# Pc_z80_senza_arduino.net
KiCad netlist of a schematic drawn in EasyEDA
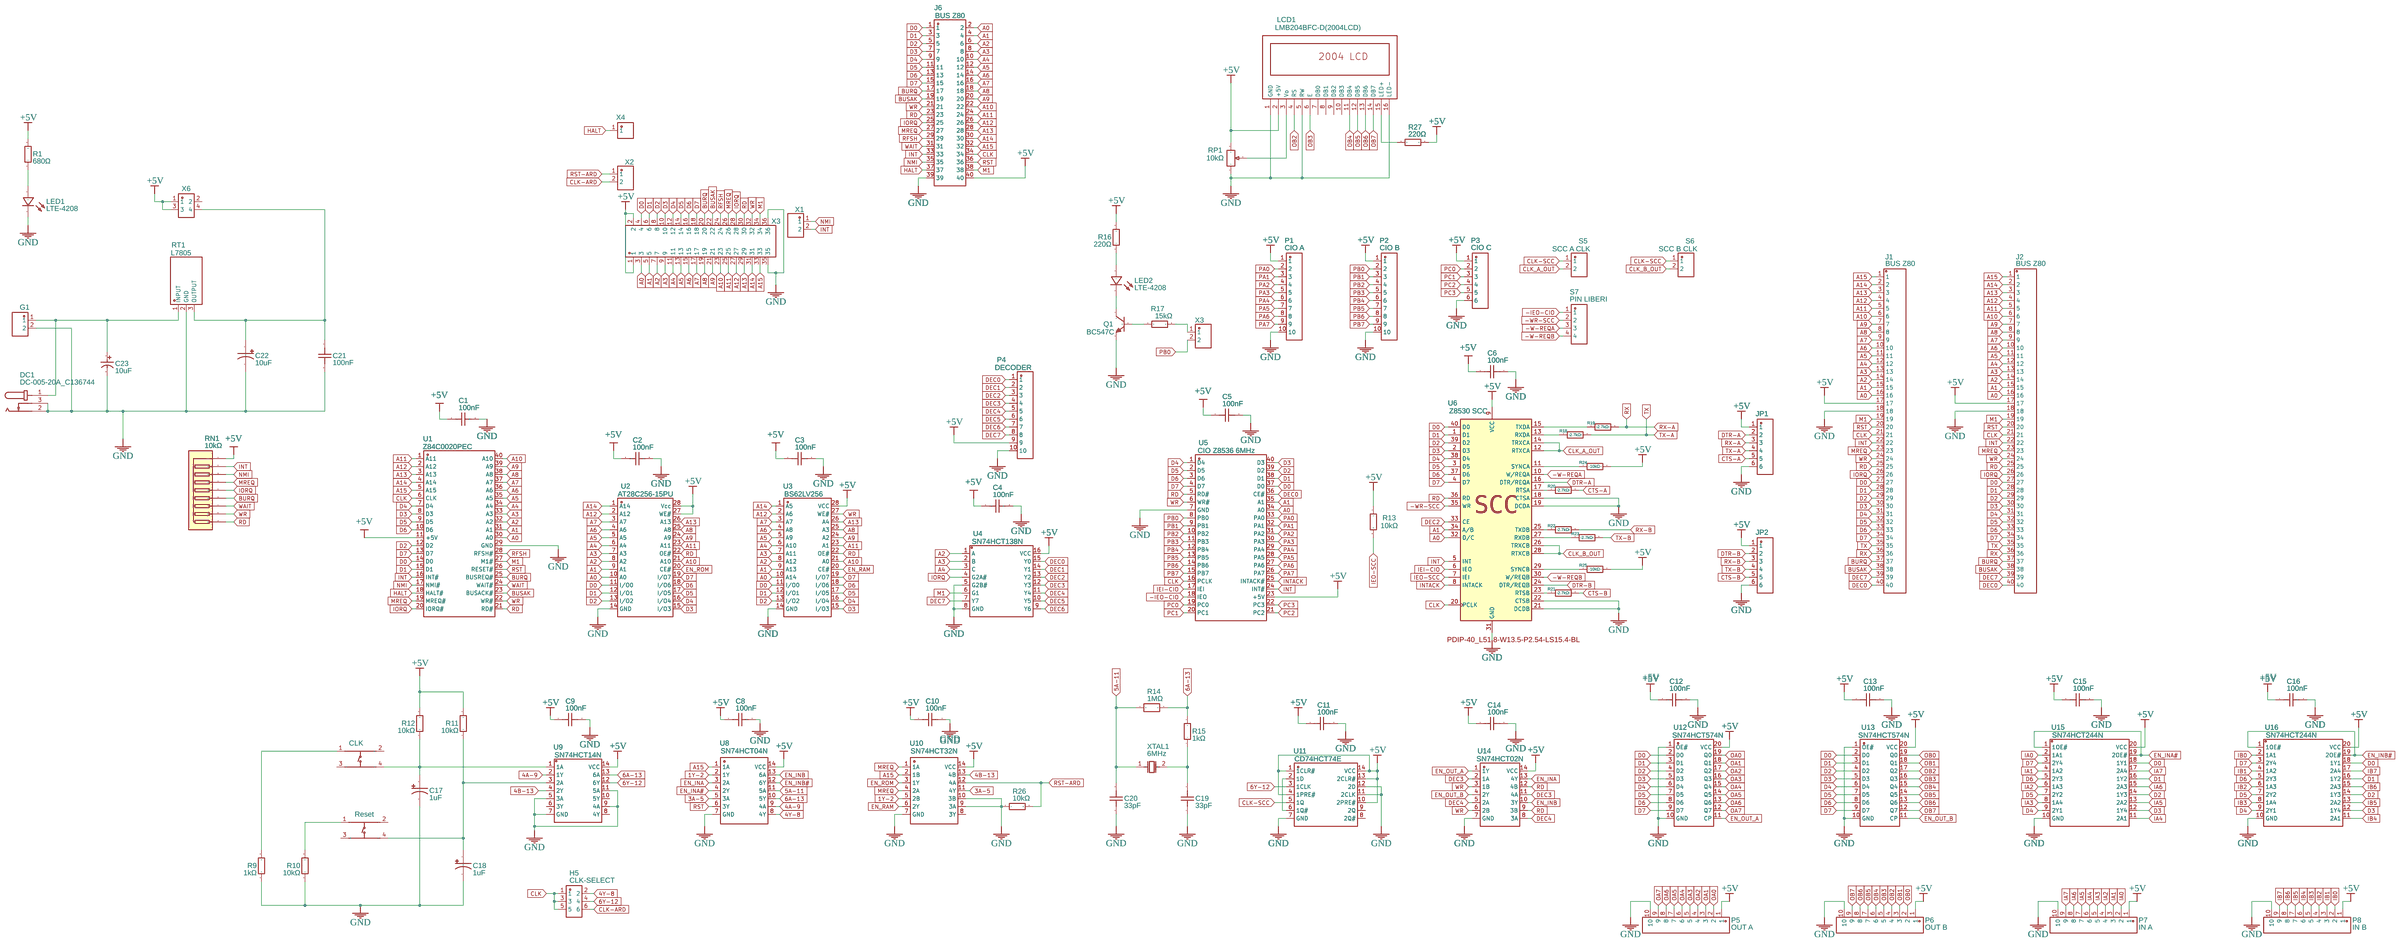
[diagram p0: schematic sheet]

(export (version "E")
  (design (tool "Eeschema 10.0.6"))
  (components
    (comp (ref "C1")
      (value "100nF")
      (fields (field (name "Manufacturer Part") "82CL0113") (field (name "Manufacturer") "KNSCHA(科尼盛)"))
      (libsource (lib "") (part "82CL0113"))
    )
    (comp (ref "C2")
      (value "100nF")
      (fields (field (name "Manufacturer Part") "82CL0113") (field (name "Manufacturer") "KNSCHA(科尼盛)"))
      (libsource (lib "") (part "82CL0113"))
    )
    (comp (ref "C3")
      (value "100nF")
      (fields (field (name "Manufacturer Part") "82CL0113") (field (name "Manufacturer") "KNSCHA(科尼盛)"))
      (libsource (lib "") (part "82CL0113"))
    )
    (comp (ref "C4")
      (value "100nF")
      (fields (field (name "Manufacturer Part") "82CL0113") (field (name "Manufacturer") "KNSCHA(科尼盛)"))
      (libsource (lib "") (part "82CL0113"))
    )
    (comp (ref "C5")
      (value "100nF")
      (fields (field (name "Manufacturer Part") "82CL0113") (field (name "Manufacturer") "KNSCHA(科尼盛)"))
      (libsource (lib "") (part "82CL0113"))
    )
    (comp (ref "C6")
      (value "100nF")
      (fields (field (name "Manufacturer Part") "82CL0113") (field (name "Manufacturer") "KNSCHA(科尼盛)"))
      (libsource (lib "") (part "82CL0113"))
    )
    (comp (ref "C8")
      (value "100nF")
      (fields (field (name "Manufacturer Part") "82CL0113") (field (name "Manufacturer") "KNSCHA(科尼盛)"))
      (libsource (lib "") (part "82CL0113"))
    )
    (comp (ref "C9")
      (value "100nF")
      (fields (field (name "Manufacturer Part") "82CL0113") (field (name "Manufacturer") "KNSCHA(科尼盛)"))
      (libsource (lib "") (part "82CL0113"))
    )
    (comp (ref "C10")
      (value "100nF")
      (fields (field (name "Manufacturer Part") "82CL0113") (field (name "Manufacturer") "KNSCHA(科尼盛)"))
      (libsource (lib "") (part "82CL0113"))
    )
    (comp (ref "C11")
      (value "100nF")
      (fields (field (name "Manufacturer Part") "82CL0113") (field (name "Manufacturer") "KNSCHA(科尼盛)"))
      (libsource (lib "") (part "82CL0113"))
    )
    (comp (ref "C12")
      (value "100nF")
      (fields (field (name "Manufacturer Part") "82CL0113") (field (name "Manufacturer") "KNSCHA(科尼盛)"))
      (libsource (lib "") (part "82CL0113"))
    )
    (comp (ref "C13")
      (value "100nF")
      (fields (field (name "Manufacturer Part") "82CL0113") (field (name "Manufacturer") "KNSCHA(科尼盛)"))
      (libsource (lib "") (part "82CL0113"))
    )
    (comp (ref "C14")
      (value "100nF")
      (fields (field (name "Manufacturer Part") "82CL0113") (field (name "Manufacturer") "KNSCHA(科尼盛)"))
      (libsource (lib "") (part "82CL0113"))
    )
    (comp (ref "C15")
      (value "100nF")
      (fields (field (name "Manufacturer Part") "82CL0113") (field (name "Manufacturer") "KNSCHA(科尼盛)"))
      (libsource (lib "") (part "82CL0113"))
    )
    (comp (ref "C16")
      (value "100nF")
      (fields (field (name "Manufacturer Part") "82CL0113") (field (name "Manufacturer") "KNSCHA(科尼盛)"))
      (libsource (lib "") (part "82CL0113"))
    )
    (comp (ref "C17")
      (value "1uF")
      (fields
        (field (name "Manufacturer Part") "RC050M1R0LO5*11TH-2A1E")
        (field (name "Manufacturer") "BERYL(绿宝石)")
      )
      (libsource (lib "") (part "RC050M1R0LO5*11TH-2A1E"))
    )
    (comp (ref "C18")
      (value "1uF")
      (fields
        (field (name "Manufacturer Part") "RC050M1R0LO5*11TH-2A1E")
        (field (name "Manufacturer") "BERYL(绿宝石)")
      )
      (libsource (lib "") (part "RC050M1R0LO5*11TH-2A1E_1"))
    )
    (comp (ref "C19")
      (value "33pF")
      (fields (field (name "Manufacturer Part") "K330J15C0GF5TL2") (field (name "Manufacturer") "VISHAY(威世)"))
      (libsource (lib "") (part "K330J15C0GF5TL2"))
    )
    (comp (ref "C20")
      (value "33pF")
      (fields (field (name "Manufacturer Part") "K330J15C0GF5TL2") (field (name "Manufacturer") "VISHAY(威世)"))
      (libsource (lib "") (part "K330J15C0GF5TL2"))
    )
    (comp (ref "C21")
      (value "100nF")
      (fields (field (name "Manufacturer Part") "82CL0113") (field (name "Manufacturer") "KNSCHA(科尼盛)"))
      (libsource (lib "") (part "82CL0113_1"))
    )
    (comp (ref "C22")
      (value "10uF")
      (fields
        (field (name "Manufacturer Part") "6.3MS510MEFCTZ4X5")
        (field (name "Manufacturer") "rubycon(红宝石)")
      )
      (libsource (lib "") (part "6.3MS510MEFCTZ4X5"))
    )
    (comp (ref "C23")
      (value "10uF")
      (fields
        (field (name "Manufacturer Part") "KM106M016D11RR0VH2FP0")
        (field (name "Manufacturer") "CX(承兴)")
      )
      (libsource (lib "") (part "10uF 16V 5*11"))
    )
    (comp (ref "DC1")
      (value "DC-005-20A_C136744")
      (fields (field (name "Manufacturer Part") "DC-005-20A") (field (name "Manufacturer") "韩国韩荣"))
      (libsource (lib "") (part "DC-005-20A_C136744"))
    )
    (comp (ref "H2")
      (value "X3")
      (fields
        (field (name "Manufacturer Part") "PZ254-2-18-Z-8.5")
        (field (name "Manufacturer") "HCTL(华灿天禄)")
      )
      (libsource (lib "") (part "PZ254-2-18-Z-8.5"))
    )
    (comp (ref "H3")
      (value "X1")
      (fields (field (name "Manufacturer Part") "PZ254V-11-02P") (field (name "Manufacturer") "XFCN(兴飞)"))
      (libsource (lib "") (part "PZ254V-11-02P"))
    )
    (comp (ref "H4")
      (value "X2")
      (fields (field (name "Manufacturer Part") "PZ254V-11-02P") (field (name "Manufacturer") "XFCN(兴飞)"))
      (libsource (lib "") (part "PZ254V-11-02P_1"))
    )
    (comp (ref "H5")
      (value "CLK-SELECT")
      (fields (field (name "Manufacturer Part") "PZ254V-12-6P") (field (name "Manufacturer") "XFCN(兴飞)"))
      (libsource (lib "") (part "PZ254V-12-6P"))
    )
    (comp (ref "H6")
      (value "X3")
      (fields (field (name "Manufacturer Part") "PZ254V-11-02P") (field (name "Manufacturer") "XFCN(兴飞)"))
      (libsource (lib "") (part "PZ254V-11-02P_1"))
    )
    (comp (ref "H7")
      (value "JP1")
      (fields (field (name "Manufacturer Part") "PM254V-11-06-H85") (field (name "Manufacturer") "XFCN(兴飞)"))
      (libsource (lib "") (part "PM254V-11-06-H85"))
    )
    (comp (ref "H8")
      (value "JP2")
      (fields (field (name "Manufacturer Part") "PM254V-11-06-H85") (field (name "Manufacturer") "XFCN(兴飞)"))
      (libsource (lib "") (part "PM254V-11-06-H85"))
    )
    (comp (ref "J1")
      (value "BUS Z80")
      (fields
        (field (name "Manufacturer Part") "2.54-1*40P母高5.7")
        (field (name "Manufacturer") "BOOMELE(博穆精密)")
      )
      (libsource (lib "") (part "2.54MM1*40HEIGHT5.7MM"))
    )
    (comp (ref "J2")
      (value "BUS Z80")
      (fields
        (field (name "Manufacturer Part") "2.54-1*40P母高5.7")
        (field (name "Manufacturer") "BOOMELE(博穆精密)")
      )
      (libsource (lib "") (part "2.54MM1*40HEIGHT5.7MM"))
    )
    (comp (ref "J6")
      (value "BUS Z80")
      (fields (field (name "Manufacturer Part") "PZ2.54-2*20") (field (name "Manufacturer") "ZHOURI(洲日)"))
      (libsource (lib "") (part "PZ2.54-2*20"))
    )
    (comp (ref "LCD1")
      (value "LMB204BFC-D(2004LCD)")
      (fields (field (name "Manufacturer") "TOPWAY"))
      (libsource (lib "") (part "LMB204BFC-D(2004LCD)"))
    )
    (comp (ref "LED1")
      (value "LTE-4208")
      (fields (field (name "Manufacturer") "LITEON(光宝)"))
      (libsource (lib "") (part "LTE-4208"))
    )
    (comp (ref "LED2")
      (value "LTE-4208")
      (fields (field (name "Manufacturer") "LITEON(光宝)"))
      (libsource (lib "") (part "LTE-4208"))
    )
    (comp (ref "P1")
      (value "CIO A")
      (fields (field (name "Manufacturer Part") "PM2.54-1*10") (field (name "Manufacturer") "ZHOURI(洲日)"))
      (libsource (lib "") (part "PM2.54-1*10_1"))
    )
    (comp (ref "P2")
      (value "CIO B")
      (fields (field (name "Manufacturer Part") "PM2.54-1*10") (field (name "Manufacturer") "ZHOURI(洲日)"))
      (libsource (lib "") (part "PM2.54-1*10_1"))
    )
    (comp (ref "P3")
      (value "CIO C")
      (fields (field (name "Manufacturer Part") "2.54-1*6P母") (field (name "Manufacturer") "BOOMELE(博穆精密)"))
      (libsource (lib "") (part "Header-Female-2.54_1x6"))
    )
    (comp (ref "P4")
      (value "DECODER")
      (fields (field (name "Manufacturer Part") "PM2.54-1*10") (field (name "Manufacturer") "ZHOURI(洲日)"))
      (libsource (lib "") (part "PM2.54-1*10_1"))
    )
    (comp (ref "P5")
      (value "OUT A")
      (fields (field (name "Manufacturer Part") "PM2.54-1*10") (field (name "Manufacturer") "ZHOURI(洲日)"))
      (libsource (lib "") (part "PM2.54-1*10"))
    )
    (comp (ref "P6")
      (value "OUT B")
      (fields (field (name "Manufacturer Part") "PM2.54-1*10") (field (name "Manufacturer") "ZHOURI(洲日)"))
      (libsource (lib "") (part "PM2.54-1*10"))
    )
    (comp (ref "P7")
      (value "IN A")
      (fields (field (name "Manufacturer Part") "PM2.54-1*10") (field (name "Manufacturer") "ZHOURI(洲日)"))
      (libsource (lib "") (part "PM2.54-1*10"))
    )
    (comp (ref "P8")
      (value "IN B")
      (fields (field (name "Manufacturer Part") "PM2.54-1*10") (field (name "Manufacturer") "ZHOURI(洲日)"))
      (libsource (lib "") (part "PM2.54-1*10"))
    )
    (comp (ref "Q1")
      (value "BC547C")
      (fields (field (name "Manufacturer") "LGE(鲁光)"))
      (libsource (lib "") (part "BC547C"))
    )
    (comp (ref "R1")
      (value "680Ω")
      (fields (field (name "Manufacturer Part") "CF1/4W-680Ω±5% T") (field (name "Manufacturer") "CCO(千志电子)"))
      (libsource (lib "") (part "CF1/4W-680Ω±5% T52"))
    )
    (comp (ref "R9")
      (value "1kΩ")
      (fields (field (name "Manufacturer Part") "CF1/4W-1KΩ±5% T") (field (name "Manufacturer") "CCO(千志电子)"))
      (libsource (lib "") (part "CF1/4W-1KΩ±5% T52"))
    )
    (comp (ref "R10")
      (value "10kΩ")
      (fields (field (name "Manufacturer Part") "CF1/4W-1KΩ±5% T") (field (name "Manufacturer") "CCO(千志电子)"))
      (libsource (lib "") (part "CF1/4W-1KΩ±5% T52"))
    )
    (comp (ref "R11")
      (value "10kΩ")
      (fields (field (name "Manufacturer Part") "CF1/4W-1KΩ±5% T") (field (name "Manufacturer") "CCO(千志电子)"))
      (libsource (lib "") (part "CF1/4W-1KΩ±5% T52"))
    )
    (comp (ref "R12")
      (value "10kΩ")
      (fields (field (name "Manufacturer Part") "CF1/4W-1KΩ±5% T") (field (name "Manufacturer") "CCO(千志电子)"))
      (libsource (lib "") (part "CF1/4W-1KΩ±5% T52"))
    )
    (comp (ref "R13")
      (value "10kΩ")
      (fields (field (name "Manufacturer Part") "CF1/4W-1KΩ±5% T") (field (name "Manufacturer") "CCO(千志电子)"))
      (libsource (lib "") (part "CF1/4W-1KΩ±5% T52_2"))
    )
    (comp (ref "R14")
      (value "1MΩ")
      (fields (field (name "Manufacturer Part") "MF1/4W-1M±1%-OT52") (field (name "Manufacturer") "VO(翔胜)"))
      (libsource (lib "") (part "MF1/4W-1M±1%-OT52"))
    )
    (comp (ref "R15")
      (value "1kΩ")
      (fields
        (field (name "Manufacturer Part") "MO1/2WS-220K±5%-ST52")
        (field (name "Manufacturer") "VO(翔胜)")
      )
      (libsource (lib "") (part "MO1/2WS-220K±5%-ST52_1"))
    )
    (comp (ref "R16")
      (value "220Ω")
      (fields (field (name "Manufacturer Part") "CF1/4W-1KΩ±5% T") (field (name "Manufacturer") "CCO(千志电子)"))
      (libsource (lib "") (part "CF1/4W-1KΩ±5% T52"))
    )
    (comp (ref "R17")
      (value "15kΩ")
      (fields (field (name "Manufacturer Part") "CF1/4W-1KΩ±5% T") (field (name "Manufacturer") "CCO(千志电子)"))
      (libsource (lib "") (part "CF1/4W-1KΩ±5% T52_1"))
    )
    (comp (ref "R18")
      (value "2.7kΩ")
      (fields (field (name "Manufacturer Part") "CF1/4W-1KΩ±5% T") (field (name "Manufacturer") "CCO(千志电子)"))
      (libsource (lib "") (part "CF1/4W-1KΩ±5% T52_1"))
    )
    (comp (ref "R19")
      (value "2.7kΩ")
      (fields (field (name "Manufacturer Part") "CF1/4W-1KΩ±5% T") (field (name "Manufacturer") "CCO(千志电子)"))
      (libsource (lib "") (part "CF1/4W-1KΩ±5% T52_1"))
    )
    (comp (ref "R20")
      (value "2.7kΩ")
      (fields (field (name "Manufacturer Part") "CF1/4W-1KΩ±5% T") (field (name "Manufacturer") "CCO(千志电子)"))
      (libsource (lib "") (part "CF1/4W-1KΩ±5% T52_1"))
    )
    (comp (ref "R21")
      (value "2.7kΩ")
      (fields (field (name "Manufacturer Part") "CF1/4W-1KΩ±5% T") (field (name "Manufacturer") "CCO(千志电子)"))
      (libsource (lib "") (part "CF1/4W-1KΩ±5% T52_1"))
    )
    (comp (ref "R22")
      (value "2.7kΩ")
      (fields (field (name "Manufacturer Part") "CF1/4W-1KΩ±5% T") (field (name "Manufacturer") "CCO(千志电子)"))
      (libsource (lib "") (part "CF1/4W-1KΩ±5% T52_1"))
    )
    (comp (ref "R23")
      (value "2.7kΩ")
      (fields (field (name "Manufacturer Part") "CF1/4W-1KΩ±5% T") (field (name "Manufacturer") "CCO(千志电子)"))
      (libsource (lib "") (part "CF1/4W-1KΩ±5% T52_1"))
    )
    (comp (ref "R24")
      (value "10kΩ")
      (fields (field (name "Manufacturer Part") "CF1/4W-1KΩ±5% T") (field (name "Manufacturer") "CCO(千志电子)"))
      (libsource (lib "") (part "CF1/4W-1KΩ±5% T52_1"))
    )
    (comp (ref "R25")
      (value "10kΩ")
      (fields (field (name "Manufacturer Part") "CF1/4W-1KΩ±5% T") (field (name "Manufacturer") "CCO(千志电子)"))
      (libsource (lib "") (part "CF1/4W-1KΩ±5% T52_1"))
    )
    (comp (ref "R26")
      (value "10kΩ")
      (fields
        (field (name "Manufacturer Part") "MO1/2WS-220K±5%-ST52")
        (field (name "Manufacturer") "VO(翔胜)")
      )
      (libsource (lib "") (part "MO1/2WS-220K±5%-ST52"))
    )
    (comp (ref "R27")
      (value "220Ω")
      (fields (field (name "Manufacturer Part") "MF1/4W-100K±1%-OT26") (field (name "Manufacturer") "VO(翔胜)"))
      (libsource (lib "") (part "MF1/4W-100K±1%-OT26"))
    )
    (comp (ref "RN1")
      (value "10kΩ")
      (fields (field (name "Manufacturer Part") "A09-103JP") (field (name "Manufacturer") "FH(风华)"))
      (libsource (lib "") (part "A09-103JP"))
    )
    (comp (ref "RP1")
      (value "10kΩ")
      (fields (field (name "Manufacturer Part") "3362P-1-202") (field (name "Manufacturer") "BOCHEN(博晨)"))
      (libsource (lib "") (part "3362P-1-202_C118929"))
    )
    (comp (ref "RT1")
      (value "L7805")
      (fields (field (name "Manufacturer") "OSEN(欧芯)"))
      (libsource (lib "") (part "L7805_C22378639"))
    )
    (comp (ref "S5")
      (value "SCC A CLK")
      (fields
        (field (name "Manufacturer Part") "ZX-PM2.54-1-2PY")
        (field (name "Manufacturer") "Megastar(兆星)")
      )
      (libsource (lib "") (part "ZX-PM2.54-1-2PY"))
    )
    (comp (ref "S6")
      (value "SCC B CLK")
      (fields
        (field (name "Manufacturer Part") "ZX-PM2.54-1-2PY")
        (field (name "Manufacturer") "Megastar(兆星)")
      )
      (libsource (lib "") (part "ZX-PM2.54-1-2PY"))
    )
    (comp (ref "S7")
      (value "PIN LIBERI")
      (fields (field (name "Manufacturer Part") "2.54-1*4P母") (field (name "Manufacturer") "BOOMELE(博穆精密)"))
      (libsource (lib "") (part "2.54-1*4P母"))
    )
    (comp (ref "SW1")
      (value "Reset")
      (fields (field (name "Manufacturer Part") "TS665CJ") (field (name "Manufacturer") "SHOU HAN(首韩)"))
      (libsource (lib "") (part "TS665CJ"))
    )
    (comp (ref "SW4")
      (value "CLK")
      (fields (field (name "Manufacturer Part") "TS665CJ") (field (name "Manufacturer") "SHOU HAN(首韩)"))
      (libsource (lib "") (part "TS665CJ"))
    )
    (comp (ref "U1")
      (value "Z84C0020PEC")
      (fields (field (name "Manufacturer Part") "Z84C0008PEG") (field (name "Manufacturer") "Zilog"))
      (libsource (lib "") (part "Z84C0008PEG"))
    )
    (comp (ref "U2")
      (value "AT28C256-15PU")
      (fields (field (name "Manufacturer") "MICROCHIP(美国微芯)"))
      (libsource (lib "") (part "AT28C256-15PU"))
    )
    (comp (ref "U3")
      (value "BS62LV256")
      (fields
        (field (name "Manufacturer Part") "CY62256NL-70PC")
        (field (name "Manufacturer") "Infineon/CYPRESS(赛普拉斯)")
      )
      (libsource (lib "") (part "CY62256NL-70PC"))
    )
    (comp (ref "U4")
      (value "SN74HCT138N")
      (fields (field (name "Manufacturer") "TI(德州仪器)"))
      (libsource (lib "") (part "SN74HCT138N"))
    )
    (comp (ref "U5")
      (value "CIO Z8536 6MHz")
      (fields (field (name "Manufacturer Part") "Z0853606PSG") (field (name "Manufacturer") "Zilog"))
      (libsource (lib "") (part "Z0853606PSG"))
    )
    (comp (ref "U6") (value "Z8530 SCC") (libsource (lib "") (part "Z8530-RESCUE-SERIALIO")))
    (comp (ref "U8")
      (value "SN74HCT04N")
      (fields (field (name "Manufacturer") "TI(德州仪器)"))
      (libsource (lib "") (part "SN74HCT04N"))
    )
    (comp (ref "U9")
      (value "SN74HCT14N")
      (fields (field (name "Manufacturer") "TI(德州仪器)"))
      (libsource (lib "") (part "SN74HCT14N"))
    )
    (comp (ref "U10")
      (value "SN74HCT32N")
      (fields (field (name "Manufacturer") "TI(德州仪器)"))
      (libsource (lib "") (part "SN74HCT32N"))
    )
    (comp (ref "U11")
      (value "CD74HCT74E")
      (fields (field (name "Manufacturer") "TI(德州仪器)"))
      (libsource (lib "") (part "CD74HCT74E"))
    )
    (comp (ref "U12")
      (value "SN74HCT574N")
      (fields (field (name "Manufacturer") "TI(德州仪器)"))
      (libsource (lib "") (part "SN74HCT574N"))
    )
    (comp (ref "U13")
      (value "SN74HCT574N")
      (fields (field (name "Manufacturer") "TI(德州仪器)"))
      (libsource (lib "") (part "SN74HCT574N"))
    )
    (comp (ref "U14")
      (value "SN74HCT02N")
      (fields (field (name "Manufacturer") "TI(德州仪器)"))
      (libsource (lib "") (part "SN74HCT02N"))
    )
    (comp (ref "U15")
      (value "SN74HCT244N")
      (fields (field (name "Manufacturer") "TI(德州仪器)"))
      (libsource (lib "") (part "SN74HCT244N"))
    )
    (comp (ref "U16")
      (value "SN74HCT244N")
      (fields (field (name "Manufacturer") "TI(德州仪器)"))
      (libsource (lib "") (part "SN74HCT244N"))
    )
    (comp (ref "X4")
      (value "X4")
      (fields
        (field (name "Manufacturer Part") "X5511FV-01-C30D97-0970")
        (field (name "Manufacturer") "XKB Connectivity(中国星坤)")
      )
      (libsource (lib "") (part "X5511FV-01-C30D97-0970"))
    )
    (comp (ref "X5")
      (value "G1")
      (fields
        (field (name "Manufacturer Part") "ZX-PZ2.54-1-2PZZ")
        (field (name "Manufacturer") "Megastar(兆星)")
      )
      (libsource (lib "") (part "ZX-PZ2.54-1-2PZZ"))
    )
    (comp (ref "X6")
      (value "X6")
      (fields (field (name "Manufacturer Part") "PZ254V-12-4P") (field (name "Manufacturer") "XFCN(兴飞)"))
      (libsource (lib "") (part "PZ254V-12-4P"))
    )
    (comp (ref "XTAL1")
      (value "6MHz")
      (fields (field (name "Manufacturer Part") "ECS-60-32-4X") (field (name "Manufacturer") "ECS"))
      (libsource (lib "") (part "ECS-60-32-4X"))
    )
  )
  (nets
    (net (code "1") (name "+5V") (class "Default")
      (node (ref "C1") (pin "1") (pinfunction "1_1") (pintype "unspecified"))
      (node (ref "C10") (pin "1") (pinfunction "1_1") (pintype "unspecified"))
      (node (ref "C11") (pin "1") (pinfunction "1_1") (pintype "unspecified"))
      (node (ref "C12") (pin "1") (pinfunction "1_1") (pintype "unspecified"))
      (node (ref "C13") (pin "1") (pinfunction "1_1") (pintype "unspecified"))
      (node (ref "C14") (pin "1") (pinfunction "1_1") (pintype "unspecified"))
      (node (ref "C15") (pin "1") (pinfunction "1_1") (pintype "unspecified"))
      (node (ref "C16") (pin "1") (pinfunction "1_1") (pintype "unspecified"))
      (node (ref "C2") (pin "1") (pinfunction "1_1") (pintype "unspecified"))
      (node (ref "C3") (pin "1") (pinfunction "1_1") (pintype "unspecified"))
      (node (ref "C4") (pin "1") (pinfunction "1_1") (pintype "unspecified"))
      (node (ref "C5") (pin "1") (pinfunction "1_1") (pintype "unspecified"))
      (node (ref "C6") (pin "1") (pinfunction "1_1") (pintype "unspecified"))
      (node (ref "C8") (pin "1") (pinfunction "1_1") (pintype "unspecified"))
      (node (ref "C9") (pin "1") (pinfunction "1_1") (pintype "unspecified"))
      (node (ref "H2") (pin "1") (pinfunction "1_1") (pintype "unspecified"))
      (node (ref "H2") (pin "2") (pinfunction "2_2") (pintype "unspecified"))
      (node (ref "H7") (pin "1") (pinfunction "1_1") (pintype "unspecified"))
      (node (ref "H8") (pin "1") (pinfunction "1_1") (pintype "unspecified"))
      (node (ref "J1") (pin "17") (pinfunction "17_17") (pintype "unspecified"))
      (node (ref "J2") (pin "17") (pinfunction "17_17") (pintype "unspecified"))
      (node (ref "J6") (pin "40") (pinfunction "40_40") (pintype "unspecified"))
      (node (ref "LCD1") (pin "2") (pinfunction "+5V_2") (pintype "unspecified"))
      (node (ref "P1") (pin "1") (pinfunction "1_1") (pintype "unspecified"))
      (node (ref "P2") (pin "1") (pinfunction "1_1") (pintype "unspecified"))
      (node (ref "P3") (pin "1") (pinfunction "1_1") (pintype "unspecified"))
      (node (ref "P4") (pin "9") (pinfunction "9_9") (pintype "unspecified"))
      (node (ref "P5") (pin "1") (pinfunction "1_1") (pintype "unspecified"))
      (node (ref "P6") (pin "1") (pinfunction "1_1") (pintype "unspecified"))
      (node (ref "P7") (pin "1") (pinfunction "1_1") (pintype "unspecified"))
      (node (ref "P8") (pin "1") (pinfunction "1_1") (pintype "unspecified"))
      (node (ref "R1") (pin "2") (pinfunction "2_2") (pintype "input"))
      (node (ref "R11") (pin "2") (pinfunction "2_2") (pintype "unspecified"))
      (node (ref "R12") (pin "2") (pinfunction "2_2") (pintype "unspecified"))
      (node (ref "R13") (pin "1") (pinfunction "1_1") (pintype "unspecified"))
      (node (ref "R16") (pin "2") (pinfunction "2_2") (pintype "unspecified"))
      (node (ref "R24") (pin "2") (pinfunction "2_2") (pintype "unspecified"))
      (node (ref "R25") (pin "2") (pinfunction "2_2") (pintype "unspecified"))
      (node (ref "R27") (pin "2") (pinfunction "2_2") (pintype "unspecified"))
      (node (ref "RN1") (pin "1") (pinfunction "1_1") (pintype "input"))
      (node (ref "RP1") (pin "3") (pinfunction "3_3") (pintype "input"))
      (node (ref "U1") (pin "11") (pinfunction "+5V_11") (pintype "unspecified"))
      (node (ref "U10") (pin "14") (pinfunction "VCC_14") (pintype "unspecified"))
      (node (ref "U11") (pin "1") (pinfunction "1CLR#_1") (pintype "unspecified"))
      (node (ref "U11") (pin "10") (pinfunction "2PRE#_10") (pintype "unspecified"))
      (node (ref "U11") (pin "13") (pinfunction "2CLR#_13") (pintype "unspecified"))
      (node (ref "U11") (pin "14") (pinfunction "VCC_14") (pintype "unspecified"))
      (node (ref "U11") (pin "4") (pinfunction "1PRE#_4") (pintype "unspecified"))
      (node (ref "U12") (pin "20") (pinfunction "VCC_20") (pintype "unspecified"))
      (node (ref "U13") (pin "20") (pinfunction "VCC_20") (pintype "unspecified"))
      (node (ref "U14") (pin "14") (pinfunction "VCC_14") (pintype "unspecified"))
      (node (ref "U15") (pin "20") (pinfunction "VCC_20") (pintype "unspecified"))
      (node (ref "U16") (pin "20") (pinfunction "VCC_20") (pintype "unspecified"))
      (node (ref "U2") (pin "27") (pinfunction "WE#_27") (pintype "unspecified"))
      (node (ref "U2") (pin "28") (pinfunction "Vcc_28") (pintype "unspecified"))
      (node (ref "U3") (pin "28") (pinfunction "VCC_28") (pintype "unspecified"))
      (node (ref "U4") (pin "16") (pinfunction "VCC_16") (pintype "unspecified"))
      (node (ref "U5") (pin "23") (pinfunction "+5V_23") (pintype "unspecified"))
      (node (ref "U6") (pin "9") (pinfunction "VCC_9") (pintype "unspecified"))
      (node (ref "U8") (pin "14") (pinfunction "VCC_14") (pintype "unspecified"))
      (node (ref "U9") (pin "14") (pinfunction "VCC_14") (pintype "unspecified"))
      (node (ref "X6") (pin "1") (pinfunction "1_1") (pintype "unspecified"))
      (node (ref "X6") (pin "3") (pinfunction "3_3") (pintype "unspecified"))
    )
    (net (code "2") (name "-IEO-CIO") (class "Default")
      (node (ref "S7") (pin "1") (pinfunction "1_1") (pintype "unspecified"))
      (node (ref "U5") (pin "18") (pinfunction "IEO_18") (pintype "unspecified"))
    )
    (net (code "3") (name "-W-REQA") (class "Default")
      (node (ref "S7") (pin "3") (pinfunction "3_3") (pintype "unspecified"))
      (node (ref "U6") (pin "10") (pinfunction "W/REQA_10") (pintype "output"))
    )
    (net (code "4") (name "-W-REQB") (class "Default")
      (node (ref "S7") (pin "4") (pinfunction "4_4") (pintype "unspecified"))
      (node (ref "U6") (pin "30") (pinfunction "W/REQB_30") (pintype "output"))
    )
    (net (code "5") (name "-WR-SCC") (class "Default")
      (node (ref "S7") (pin "2") (pinfunction "2_2") (pintype "unspecified"))
      (node (ref "U6") (pin "35") (pinfunction "WR_35") (pintype "input"))
    )
    (net (code "6") (name "1Y-2") (class "Default")
      (node (ref "U10") (pin "5") (pinfunction "2B_5") (pintype "unspecified"))
      (node (ref "U8") (pin "2") (pinfunction "1Y_2") (pintype "unspecified"))
    )
    (net (code "7") (name "3A-5") (class "Default")
      (node (ref "U10") (pin "11") (pinfunction "4Y_11") (pintype "unspecified"))
      (node (ref "U8") (pin "5") (pinfunction "3A_5") (pintype "unspecified"))
    )
    (net (code "8") (name "4A-9") (class "Default")
      (node (ref "U8") (pin "9") (pinfunction "4A_9") (pintype "unspecified"))
      (node (ref "U9") (pin "2") (pinfunction "1Y_2") (pintype "unspecified"))
    )
    (net (code "9") (name "4B-13") (class "Default")
      (node (ref "U10") (pin "13") (pinfunction "4B_13") (pintype "unspecified"))
      (node (ref "U9") (pin "4") (pinfunction "2Y_4") (pintype "unspecified"))
    )
    (net (code "10") (name "4Y-8") (class "Default")
      (node (ref "H5") (pin "2") (pinfunction "2_2") (pintype "unspecified"))
      (node (ref "U8") (pin "8") (pinfunction "4Y_8") (pintype "unspecified"))
    )
    (net (code "11") (name "5A-11") (class "Default")
      (node (ref "C20") (pin "2") (pinfunction "2_2") (pintype "unspecified"))
      (node (ref "R14") (pin "1") (pinfunction "1_1") (pintype "unspecified"))
      (node (ref "U8") (pin "11") (pinfunction "5A_11") (pintype "unspecified"))
      (node (ref "XTAL1") (pin "1") (pinfunction "OSC1_1") (pintype "unspecified"))
    )
    (net (code "12") (name "6A-13") (class "Default")
      (node (ref "R14") (pin "2") (pinfunction "2_2") (pintype "unspecified"))
      (node (ref "R15") (pin "2") (pinfunction "2_2") (pintype "unspecified"))
      (node (ref "U8") (pin "10") (pinfunction "5Y_10") (pintype "unspecified"))
      (node (ref "U9") (pin "13") (pinfunction "6A_13") (pintype "unspecified"))
    )
    (net (code "13") (name "6Y-12") (class "Default")
      (node (ref "H5") (pin "4") (pinfunction "4_4") (pintype "unspecified"))
      (node (ref "U11") (pin "3") (pinfunction "1CLK_3") (pintype "unspecified"))
      (node (ref "U9") (pin "12") (pinfunction "6Y_12") (pintype "unspecified"))
    )
    (net (code "14") (name "A0") (class "Default")
      (node (ref "H2") (pin "3") (pinfunction "3_3") (pintype "unspecified"))
      (node (ref "J1") (pin "16") (pinfunction "16_16") (pintype "unspecified"))
      (node (ref "J2") (pin "16") (pinfunction "16_16") (pintype "unspecified"))
      (node (ref "J6") (pin "2") (pinfunction "2_2") (pintype "unspecified"))
      (node (ref "U1") (pin "30") (pinfunction "A0_30") (pintype "unspecified"))
      (node (ref "U2") (pin "10") (pinfunction "A0_10") (pintype "unspecified"))
      (node (ref "U3") (pin "10") (pinfunction "A14_10") (pintype "unspecified"))
      (node (ref "U5") (pin "34") (pinfunction "A0_34") (pintype "unspecified"))
      (node (ref "U6") (pin "32") (pinfunction "D/C_32") (pintype "input"))
    )
    (net (code "15") (name "A1") (class "Default")
      (node (ref "H2") (pin "5") (pinfunction "5_5") (pintype "unspecified"))
      (node (ref "J1") (pin "15") (pinfunction "15_15") (pintype "unspecified"))
      (node (ref "J2") (pin "15") (pinfunction "15_15") (pintype "unspecified"))
      (node (ref "J6") (pin "4") (pinfunction "4_4") (pintype "unspecified"))
      (node (ref "U1") (pin "31") (pinfunction "A1_31") (pintype "unspecified"))
      (node (ref "U2") (pin "9") (pinfunction "A1_9") (pintype "unspecified"))
      (node (ref "U3") (pin "9") (pinfunction "A13_9") (pintype "unspecified"))
      (node (ref "U5") (pin "35") (pinfunction "A1_35") (pintype "unspecified"))
      (node (ref "U6") (pin "34") (pinfunction "A/B_34") (pintype "input"))
    )
    (net (code "16") (name "A2") (class "Default")
      (node (ref "H2") (pin "7") (pinfunction "7_7") (pintype "unspecified"))
      (node (ref "J1") (pin "14") (pinfunction "14_14") (pintype "unspecified"))
      (node (ref "J2") (pin "14") (pinfunction "14_14") (pintype "unspecified"))
      (node (ref "J6") (pin "6") (pinfunction "6_6") (pintype "unspecified"))
      (node (ref "U1") (pin "32") (pinfunction "A2_32") (pintype "unspecified"))
      (node (ref "U2") (pin "8") (pinfunction "A2_8") (pintype "unspecified"))
      (node (ref "U3") (pin "8") (pinfunction "A12_8") (pintype "unspecified"))
      (node (ref "U4") (pin "1") (pinfunction "A_1") (pintype "unspecified"))
    )
    (net (code "17") (name "A3") (class "Default")
      (node (ref "H2") (pin "9") (pinfunction "9_9") (pintype "unspecified"))
      (node (ref "J1") (pin "13") (pinfunction "13_13") (pintype "unspecified"))
      (node (ref "J2") (pin "13") (pinfunction "13_13") (pintype "unspecified"))
      (node (ref "J6") (pin "8") (pinfunction "8_8") (pintype "unspecified"))
      (node (ref "U1") (pin "33") (pinfunction "A3_33") (pintype "unspecified"))
      (node (ref "U2") (pin "7") (pinfunction "A3_7") (pintype "unspecified"))
      (node (ref "U3") (pin "7") (pinfunction "A11_7") (pintype "unspecified"))
      (node (ref "U4") (pin "2") (pinfunction "B_2") (pintype "unspecified"))
    )
    (net (code "18") (name "A4") (class "Default")
      (node (ref "H2") (pin "11") (pinfunction "11_11") (pintype "unspecified"))
      (node (ref "J1") (pin "12") (pinfunction "12_12") (pintype "unspecified"))
      (node (ref "J2") (pin "12") (pinfunction "12_12") (pintype "unspecified"))
      (node (ref "J6") (pin "10") (pinfunction "10_10") (pintype "unspecified"))
      (node (ref "U1") (pin "34") (pinfunction "A4_34") (pintype "unspecified"))
      (node (ref "U2") (pin "6") (pinfunction "A4_6") (pintype "unspecified"))
      (node (ref "U3") (pin "6") (pinfunction "A10_6") (pintype "unspecified"))
      (node (ref "U4") (pin "3") (pinfunction "C_3") (pintype "unspecified"))
    )
    (net (code "19") (name "A5") (class "Default")
      (node (ref "H2") (pin "13") (pinfunction "13_13") (pintype "unspecified"))
      (node (ref "J1") (pin "11") (pinfunction "11_11") (pintype "unspecified"))
      (node (ref "J2") (pin "11") (pinfunction "11_11") (pintype "unspecified"))
      (node (ref "J6") (pin "12") (pinfunction "12_12") (pintype "unspecified"))
      (node (ref "U1") (pin "35") (pinfunction "A5_35") (pintype "unspecified"))
      (node (ref "U2") (pin "5") (pinfunction "A5_5") (pintype "unspecified"))
      (node (ref "U3") (pin "5") (pinfunction "A9_5") (pintype "unspecified"))
    )
    (net (code "20") (name "A6") (class "Default")
      (node (ref "H2") (pin "15") (pinfunction "15_15") (pintype "unspecified"))
      (node (ref "J1") (pin "10") (pinfunction "10_10") (pintype "unspecified"))
      (node (ref "J2") (pin "10") (pinfunction "10_10") (pintype "unspecified"))
      (node (ref "J6") (pin "14") (pinfunction "14_14") (pintype "unspecified"))
      (node (ref "U1") (pin "36") (pinfunction "A6_36") (pintype "unspecified"))
      (node (ref "U2") (pin "4") (pinfunction "A6_4") (pintype "unspecified"))
      (node (ref "U3") (pin "4") (pinfunction "A8_4") (pintype "unspecified"))
    )
    (net (code "21") (name "A7") (class "Default")
      (node (ref "H2") (pin "17") (pinfunction "17_17") (pintype "unspecified"))
      (node (ref "J1") (pin "9") (pinfunction "9_9") (pintype "unspecified"))
      (node (ref "J2") (pin "9") (pinfunction "9_9") (pintype "unspecified"))
      (node (ref "J6") (pin "16") (pinfunction "16_16") (pintype "unspecified"))
      (node (ref "U1") (pin "37") (pinfunction "A7_37") (pintype "unspecified"))
      (node (ref "U2") (pin "3") (pinfunction "A7_3") (pintype "unspecified"))
      (node (ref "U3") (pin "3") (pinfunction "A7_3") (pintype "unspecified"))
    )
    (net (code "22") (name "A8") (class "Default")
      (node (ref "H2") (pin "19") (pinfunction "19_19") (pintype "unspecified"))
      (node (ref "J1") (pin "8") (pinfunction "8_8") (pintype "unspecified"))
      (node (ref "J2") (pin "8") (pinfunction "8_8") (pintype "unspecified"))
      (node (ref "J6") (pin "18") (pinfunction "18_18") (pintype "unspecified"))
      (node (ref "U1") (pin "38") (pinfunction "A8_38") (pintype "unspecified"))
      (node (ref "U2") (pin "25") (pinfunction "A8_25") (pintype "unspecified"))
      (node (ref "U3") (pin "25") (pinfunction "A3_25") (pintype "unspecified"))
    )
    (net (code "23") (name "A9") (class "Default")
      (node (ref "H2") (pin "21") (pinfunction "21_21") (pintype "unspecified"))
      (node (ref "J1") (pin "7") (pinfunction "7_7") (pintype "unspecified"))
      (node (ref "J2") (pin "7") (pinfunction "7_7") (pintype "unspecified"))
      (node (ref "J6") (pin "20") (pinfunction "20_20") (pintype "unspecified"))
      (node (ref "U1") (pin "39") (pinfunction "A9_39") (pintype "unspecified"))
      (node (ref "U2") (pin "24") (pinfunction "A9_24") (pintype "unspecified"))
      (node (ref "U3") (pin "24") (pinfunction "A2_24") (pintype "unspecified"))
    )
    (net (code "24") (name "A10") (class "Default")
      (node (ref "H2") (pin "23") (pinfunction "23_23") (pintype "unspecified"))
      (node (ref "J1") (pin "6") (pinfunction "6_6") (pintype "unspecified"))
      (node (ref "J2") (pin "6") (pinfunction "6_6") (pintype "unspecified"))
      (node (ref "J6") (pin "22") (pinfunction "22_22") (pintype "unspecified"))
      (node (ref "U1") (pin "40") (pinfunction "A10_40") (pintype "unspecified"))
      (node (ref "U2") (pin "21") (pinfunction "A10_21") (pintype "unspecified"))
      (node (ref "U3") (pin "21") (pinfunction "A0_21") (pintype "unspecified"))
    )
    (net (code "25") (name "A11") (class "Default")
      (node (ref "H2") (pin "25") (pinfunction "25_25") (pintype "unspecified"))
      (node (ref "J1") (pin "5") (pinfunction "5_5") (pintype "unspecified"))
      (node (ref "J2") (pin "5") (pinfunction "5_5") (pintype "unspecified"))
      (node (ref "J6") (pin "24") (pinfunction "24_24") (pintype "unspecified"))
      (node (ref "U1") (pin "1") (pinfunction "A11_1") (pintype "unspecified"))
      (node (ref "U2") (pin "23") (pinfunction "A11_23") (pintype "unspecified"))
      (node (ref "U3") (pin "23") (pinfunction "A1_23") (pintype "unspecified"))
    )
    (net (code "26") (name "A12") (class "Default")
      (node (ref "H2") (pin "27") (pinfunction "27_27") (pintype "unspecified"))
      (node (ref "J1") (pin "4") (pinfunction "4_4") (pintype "unspecified"))
      (node (ref "J2") (pin "4") (pinfunction "4_4") (pintype "unspecified"))
      (node (ref "J6") (pin "26") (pinfunction "26_26") (pintype "unspecified"))
      (node (ref "U1") (pin "2") (pinfunction "A12_2") (pintype "unspecified"))
      (node (ref "U2") (pin "2") (pinfunction "A12_2") (pintype "unspecified"))
      (node (ref "U3") (pin "2") (pinfunction "A6_2") (pintype "unspecified"))
    )
    (net (code "27") (name "A13") (class "Default")
      (node (ref "H2") (pin "29") (pinfunction "29_29") (pintype "unspecified"))
      (node (ref "J1") (pin "3") (pinfunction "3_3") (pintype "unspecified"))
      (node (ref "J2") (pin "3") (pinfunction "3_3") (pintype "unspecified"))
      (node (ref "J6") (pin "28") (pinfunction "28_28") (pintype "unspecified"))
      (node (ref "U1") (pin "3") (pinfunction "A13_3") (pintype "unspecified"))
      (node (ref "U2") (pin "26") (pinfunction "A13_26") (pintype "unspecified"))
      (node (ref "U3") (pin "26") (pinfunction "A4_26") (pintype "unspecified"))
    )
    (net (code "28") (name "A14") (class "Default")
      (node (ref "H2") (pin "31") (pinfunction "31_31") (pintype "unspecified"))
      (node (ref "J1") (pin "2") (pinfunction "2_2") (pintype "unspecified"))
      (node (ref "J2") (pin "2") (pinfunction "2_2") (pintype "unspecified"))
      (node (ref "J6") (pin "30") (pinfunction "30_30") (pintype "unspecified"))
      (node (ref "U1") (pin "4") (pinfunction "A14_4") (pintype "unspecified"))
      (node (ref "U2") (pin "1") (pinfunction "A14_1") (pintype "unspecified"))
      (node (ref "U3") (pin "1") (pinfunction "A5_1") (pintype "unspecified"))
    )
    (net (code "29") (name "A15") (class "Default")
      (node (ref "H2") (pin "33") (pinfunction "33_33") (pintype "unspecified"))
      (node (ref "J1") (pin "1") (pinfunction "1_1") (pintype "unspecified"))
      (node (ref "J2") (pin "1") (pinfunction "1_1") (pintype "unspecified"))
      (node (ref "J6") (pin "32") (pinfunction "32_32") (pintype "unspecified"))
      (node (ref "U1") (pin "5") (pinfunction "A15_5") (pintype "unspecified"))
      (node (ref "U10") (pin "2") (pinfunction "1B_2") (pintype "unspecified"))
      (node (ref "U8") (pin "1") (pinfunction "1A_1") (pintype "unspecified"))
    )
    (net (code "30") (name "BURQ") (class "Default")
      (node (ref "H2") (pin "20") (pinfunction "20_20") (pintype "unspecified"))
      (node (ref "J1") (pin "37") (pinfunction "37_37") (pintype "unspecified"))
      (node (ref "J2") (pin "37") (pinfunction "37_37") (pintype "unspecified"))
      (node (ref "J6") (pin "17") (pinfunction "17_17") (pintype "unspecified"))
      (node (ref "RN1") (pin "6") (pinfunction "6_6") (pintype "input"))
      (node (ref "U1") (pin "25") (pinfunction "BUSREQ#_25") (pintype "unspecified"))
    )
    (net (code "31") (name "BUSAK") (class "Default")
      (node (ref "H2") (pin "22") (pinfunction "22_22") (pintype "unspecified"))
      (node (ref "J1") (pin "38") (pinfunction "38_38") (pintype "unspecified"))
      (node (ref "J2") (pin "38") (pinfunction "38_38") (pintype "unspecified"))
      (node (ref "J6") (pin "19") (pinfunction "19_19") (pintype "unspecified"))
      (node (ref "U1") (pin "23") (pinfunction "BUSACK#_23") (pintype "unspecified"))
    )
    (net (code "32") (name "CLK") (class "Default")
      (node (ref "H5") (pin "1") (pinfunction "1_1") (pintype "unspecified"))
      (node (ref "H5") (pin "3") (pinfunction "3_3") (pintype "unspecified"))
      (node (ref "H5") (pin "5") (pinfunction "5_5") (pintype "unspecified"))
      (node (ref "J1") (pin "21") (pinfunction "21_21") (pintype "unspecified"))
      (node (ref "J2") (pin "21") (pinfunction "21_21") (pintype "unspecified"))
      (node (ref "J6") (pin "34") (pinfunction "34_34") (pintype "unspecified"))
      (node (ref "U1") (pin "6") (pinfunction "CLK_6") (pintype "unspecified"))
      (node (ref "U5") (pin "16") (pinfunction "PCLK_16") (pintype "unspecified"))
      (node (ref "U6") (pin "20") (pinfunction "PCLK_20") (pintype "input"))
    )
    (net (code "33") (name "CLK-ARD") (class "Default")
      (node (ref "H4") (pin "2") (pinfunction "2_2") (pintype "unspecified"))
      (node (ref "H5") (pin "6") (pinfunction "6_6") (pintype "unspecified"))
    )
    (net (code "34") (name "CLK-SCC") (class "Default")
      (node (ref "S5") (pin "1") (pinfunction "1_1") (pintype "unspecified"))
      (node (ref "S6") (pin "1") (pinfunction "1_1") (pintype "unspecified"))
      (node (ref "U11") (pin "5") (pinfunction "1Q_5") (pintype "unspecified"))
    )
    (net (code "35") (name "CLK_A_OUT") (class "Default")
      (node (ref "S5") (pin "2") (pinfunction "2_2") (pintype "unspecified"))
      (node (ref "U6") (pin "12") (pinfunction "RTXCA_12") (pintype "input"))
      (node (ref "U6") (pin "14") (pinfunction "TRXCA_14") (pintype "bidirectional"))
    )
    (net (code "36") (name "CLK_B_OUT") (class "Default")
      (node (ref "S6") (pin "2") (pinfunction "2_2") (pintype "unspecified"))
      (node (ref "U6") (pin "26") (pinfunction "TRXCB_26") (pintype "bidirectional"))
      (node (ref "U6") (pin "28") (pinfunction "RTXCB_28") (pintype "input"))
    )
    (net (code "37") (name "CTS-A") (class "Default")
      (node (ref "H7") (pin "5") (pinfunction "5_5") (pintype "unspecified"))
      (node (ref "R20") (pin "2") (pinfunction "2_2") (pintype "unspecified"))
    )
    (net (code "38") (name "CTS-B") (class "Default")
      (node (ref "H8") (pin "5") (pinfunction "5_5") (pintype "unspecified"))
      (node (ref "R21") (pin "2") (pinfunction "2_2") (pintype "unspecified"))
    )
    (net (code "39") (name "D0") (class "Default")
      (node (ref "H2") (pin "4") (pinfunction "4_4") (pintype "unspecified"))
      (node (ref "J1") (pin "27") (pinfunction "27_27") (pintype "unspecified"))
      (node (ref "J2") (pin "27") (pinfunction "27_27") (pintype "unspecified"))
      (node (ref "J6") (pin "1") (pinfunction "1_1") (pintype "unspecified"))
      (node (ref "U1") (pin "14") (pinfunction "D0_14") (pintype "unspecified"))
      (node (ref "U12") (pin "2") (pinfunction "D0_2") (pintype "unspecified"))
      (node (ref "U13") (pin "2") (pinfunction "D0_2") (pintype "unspecified"))
      (node (ref "U15") (pin "18") (pinfunction "1Y1_18") (pintype "unspecified"))
      (node (ref "U16") (pin "18") (pinfunction "1Y1_18") (pintype "unspecified"))
      (node (ref "U2") (pin "11") (pinfunction "I/O0_11") (pintype "unspecified"))
      (node (ref "U3") (pin "11") (pinfunction "I/O0_11") (pintype "unspecified"))
      (node (ref "U5") (pin "37") (pinfunction "D0_37") (pintype "unspecified"))
      (node (ref "U6") (pin "40") (pinfunction "D0_40") (pintype "input"))
    )
    (net (code "40") (name "D1") (class "Default")
      (node (ref "H2") (pin "6") (pinfunction "6_6") (pintype "unspecified"))
      (node (ref "J1") (pin "28") (pinfunction "28_28") (pintype "unspecified"))
      (node (ref "J2") (pin "28") (pinfunction "28_28") (pintype "unspecified"))
      (node (ref "J6") (pin "3") (pinfunction "3_3") (pintype "unspecified"))
      (node (ref "U1") (pin "15") (pinfunction "D1_15") (pintype "unspecified"))
      (node (ref "U12") (pin "3") (pinfunction "D1_3") (pintype "unspecified"))
      (node (ref "U13") (pin "3") (pinfunction "D1_3") (pintype "unspecified"))
      (node (ref "U15") (pin "16") (pinfunction "1Y2_16") (pintype "unspecified"))
      (node (ref "U16") (pin "16") (pinfunction "1Y2_16") (pintype "unspecified"))
      (node (ref "U2") (pin "12") (pinfunction "I/O1_12") (pintype "unspecified"))
      (node (ref "U3") (pin "12") (pinfunction "I/O1_12") (pintype "unspecified"))
      (node (ref "U5") (pin "38") (pinfunction "D1_38") (pintype "unspecified"))
      (node (ref "U6") (pin "1") (pinfunction "D1_1") (pintype "input"))
    )
    (net (code "41") (name "D2") (class "Default")
      (node (ref "H2") (pin "8") (pinfunction "8_8") (pintype "unspecified"))
      (node (ref "J1") (pin "29") (pinfunction "29_29") (pintype "unspecified"))
      (node (ref "J2") (pin "29") (pinfunction "29_29") (pintype "unspecified"))
      (node (ref "J6") (pin "5") (pinfunction "5_5") (pintype "unspecified"))
      (node (ref "U1") (pin "12") (pinfunction "D2_12") (pintype "unspecified"))
      (node (ref "U12") (pin "4") (pinfunction "D2_4") (pintype "unspecified"))
      (node (ref "U13") (pin "4") (pinfunction "D2_4") (pintype "unspecified"))
      (node (ref "U15") (pin "14") (pinfunction "1Y3_14") (pintype "unspecified"))
      (node (ref "U16") (pin "14") (pinfunction "1Y3_14") (pintype "unspecified"))
      (node (ref "U2") (pin "13") (pinfunction "I/O2_13") (pintype "unspecified"))
      (node (ref "U3") (pin "13") (pinfunction "I/O2_13") (pintype "unspecified"))
      (node (ref "U5") (pin "39") (pinfunction "D2_39") (pintype "unspecified"))
      (node (ref "U6") (pin "39") (pinfunction "D2_39") (pintype "input"))
    )
    (net (code "42") (name "D3") (class "Default")
      (node (ref "H2") (pin "10") (pinfunction "10_10") (pintype "unspecified"))
      (node (ref "J1") (pin "30") (pinfunction "30_30") (pintype "unspecified"))
      (node (ref "J2") (pin "30") (pinfunction "30_30") (pintype "unspecified"))
      (node (ref "J6") (pin "7") (pinfunction "7_7") (pintype "unspecified"))
      (node (ref "U1") (pin "8") (pinfunction "D3_8") (pintype "unspecified"))
      (node (ref "U12") (pin "5") (pinfunction "D3_5") (pintype "unspecified"))
      (node (ref "U13") (pin "5") (pinfunction "D3_5") (pintype "unspecified"))
      (node (ref "U15") (pin "12") (pinfunction "1Y4_12") (pintype "unspecified"))
      (node (ref "U16") (pin "12") (pinfunction "1Y4_12") (pintype "unspecified"))
      (node (ref "U2") (pin "15") (pinfunction "I/O3_15") (pintype "unspecified"))
      (node (ref "U3") (pin "15") (pinfunction "I/O3_15") (pintype "unspecified"))
      (node (ref "U5") (pin "40") (pinfunction "D3_40") (pintype "unspecified"))
      (node (ref "U6") (pin "2") (pinfunction "D3_2") (pintype "input"))
    )
    (net (code "43") (name "D4") (class "Default")
      (node (ref "H2") (pin "12") (pinfunction "12_12") (pintype "unspecified"))
      (node (ref "J1") (pin "31") (pinfunction "31_31") (pintype "unspecified"))
      (node (ref "J2") (pin "31") (pinfunction "31_31") (pintype "unspecified"))
      (node (ref "J6") (pin "9") (pinfunction "9_9") (pintype "unspecified"))
      (node (ref "U1") (pin "7") (pinfunction "D4_7") (pintype "unspecified"))
      (node (ref "U12") (pin "6") (pinfunction "D4_6") (pintype "unspecified"))
      (node (ref "U13") (pin "6") (pinfunction "D4_6") (pintype "unspecified"))
      (node (ref "U15") (pin "9") (pinfunction "2Y1_9") (pintype "unspecified"))
      (node (ref "U16") (pin "9") (pinfunction "2Y1_9") (pintype "unspecified"))
      (node (ref "U2") (pin "16") (pinfunction "I/O4_16") (pintype "unspecified"))
      (node (ref "U3") (pin "16") (pinfunction "I/O4_16") (pintype "unspecified"))
      (node (ref "U5") (pin "1") (pinfunction "D4_1") (pintype "unspecified"))
      (node (ref "U6") (pin "38") (pinfunction "D4_38") (pintype "input"))
    )
    (net (code "44") (name "D5") (class "Default")
      (node (ref "H2") (pin "14") (pinfunction "14_14") (pintype "unspecified"))
      (node (ref "J1") (pin "32") (pinfunction "32_32") (pintype "unspecified"))
      (node (ref "J2") (pin "32") (pinfunction "32_32") (pintype "unspecified"))
      (node (ref "J6") (pin "11") (pinfunction "11_11") (pintype "unspecified"))
      (node (ref "U1") (pin "9") (pinfunction "D5_9") (pintype "unspecified"))
      (node (ref "U12") (pin "7") (pinfunction "D5_7") (pintype "unspecified"))
      (node (ref "U13") (pin "7") (pinfunction "D5_7") (pintype "unspecified"))
      (node (ref "U15") (pin "7") (pinfunction "2Y2_7") (pintype "unspecified"))
      (node (ref "U16") (pin "7") (pinfunction "2Y2_7") (pintype "unspecified"))
      (node (ref "U2") (pin "17") (pinfunction "I/O5_17") (pintype "unspecified"))
      (node (ref "U3") (pin "17") (pinfunction "I/O5_17") (pintype "unspecified"))
      (node (ref "U5") (pin "2") (pinfunction "D5_2") (pintype "unspecified"))
      (node (ref "U6") (pin "3") (pinfunction "D5_3") (pintype "input"))
    )
    (net (code "45") (name "D6") (class "Default")
      (node (ref "H2") (pin "16") (pinfunction "16_16") (pintype "unspecified"))
      (node (ref "J1") (pin "33") (pinfunction "33_33") (pintype "unspecified"))
      (node (ref "J2") (pin "33") (pinfunction "33_33") (pintype "unspecified"))
      (node (ref "J6") (pin "13") (pinfunction "13_13") (pintype "unspecified"))
      (node (ref "U1") (pin "10") (pinfunction "D6_10") (pintype "unspecified"))
      (node (ref "U12") (pin "8") (pinfunction "D6_8") (pintype "unspecified"))
      (node (ref "U13") (pin "8") (pinfunction "D6_8") (pintype "unspecified"))
      (node (ref "U15") (pin "5") (pinfunction "2Y3_5") (pintype "unspecified"))
      (node (ref "U16") (pin "5") (pinfunction "2Y3_5") (pintype "unspecified"))
      (node (ref "U2") (pin "18") (pinfunction "I/O6_18") (pintype "unspecified"))
      (node (ref "U3") (pin "18") (pinfunction "I/O6_18") (pintype "unspecified"))
      (node (ref "U5") (pin "3") (pinfunction "D6_3") (pintype "unspecified"))
      (node (ref "U6") (pin "37") (pinfunction "D6_37") (pintype "input"))
    )
    (net (code "46") (name "D7") (class "Default")
      (node (ref "H2") (pin "18") (pinfunction "18_18") (pintype "unspecified"))
      (node (ref "J1") (pin "34") (pinfunction "34_34") (pintype "unspecified"))
      (node (ref "J2") (pin "34") (pinfunction "34_34") (pintype "unspecified"))
      (node (ref "J6") (pin "15") (pinfunction "15_15") (pintype "unspecified"))
      (node (ref "U1") (pin "13") (pinfunction "D7_13") (pintype "unspecified"))
      (node (ref "U12") (pin "9") (pinfunction "D7_9") (pintype "unspecified"))
      (node (ref "U13") (pin "9") (pinfunction "D7_9") (pintype "unspecified"))
      (node (ref "U15") (pin "3") (pinfunction "2Y4_3") (pintype "unspecified"))
      (node (ref "U16") (pin "3") (pinfunction "2Y4_3") (pintype "unspecified"))
      (node (ref "U2") (pin "19") (pinfunction "I/O7_19") (pintype "unspecified"))
      (node (ref "U3") (pin "19") (pinfunction "I/O7_19") (pintype "unspecified"))
      (node (ref "U5") (pin "4") (pinfunction "D7_4") (pintype "unspecified"))
      (node (ref "U6") (pin "4") (pinfunction "D7_4") (pintype "input"))
    )
    (net (code "47") (name "DEC0") (class "Default")
      (node (ref "J1") (pin "40") (pinfunction "40_40") (pintype "unspecified"))
      (node (ref "J2") (pin "40") (pinfunction "40_40") (pintype "unspecified"))
      (node (ref "P4") (pin "1") (pinfunction "1_1") (pintype "unspecified"))
      (node (ref "U4") (pin "15") (pinfunction "Y0_15") (pintype "unspecified"))
      (node (ref "U5") (pin "36") (pinfunction "CE#_36") (pintype "unspecified"))
    )
    (net (code "48") (name "DEC1") (class "Default")
      (node (ref "P4") (pin "2") (pinfunction "2_2") (pintype "unspecified"))
      (node (ref "U4") (pin "14") (pinfunction "Y1_14") (pintype "unspecified"))
    )
    (net (code "49") (name "DEC2") (class "Default")
      (node (ref "P4") (pin "3") (pinfunction "3_3") (pintype "unspecified"))
      (node (ref "U4") (pin "13") (pinfunction "Y2_13") (pintype "unspecified"))
      (node (ref "U6") (pin "33") (pinfunction "CE_33") (pintype "input"))
    )
    (net (code "50") (name "DEC3") (class "Default")
      (node (ref "P4") (pin "4") (pinfunction "4_4") (pintype "unspecified"))
      (node (ref "U14") (pin "11") (pinfunction "4A_11") (pintype "unspecified"))
      (node (ref "U14") (pin "2") (pinfunction "1A_2") (pintype "unspecified"))
      (node (ref "U4") (pin "12") (pinfunction "Y3_12") (pintype "unspecified"))
    )
    (net (code "51") (name "DEC4") (class "Default")
      (node (ref "P4") (pin "5") (pinfunction "5_5") (pintype "unspecified"))
      (node (ref "U14") (pin "5") (pinfunction "2A_5") (pintype "unspecified"))
      (node (ref "U14") (pin "8") (pinfunction "3A_8") (pintype "unspecified"))
      (node (ref "U4") (pin "11") (pinfunction "Y4_11") (pintype "unspecified"))
    )
    (net (code "52") (name "DEC5") (class "Default")
      (node (ref "P4") (pin "6") (pinfunction "6_6") (pintype "unspecified"))
      (node (ref "U4") (pin "10") (pinfunction "Y5_10") (pintype "unspecified"))
    )
    (net (code "53") (name "DEC6") (class "Default")
      (node (ref "P4") (pin "7") (pinfunction "7_7") (pintype "unspecified"))
      (node (ref "U4") (pin "9") (pinfunction "Y6_9") (pintype "unspecified"))
    )
    (net (code "54") (name "DEC7") (class "Default")
      (node (ref "J1") (pin "39") (pinfunction "39_39") (pintype "unspecified"))
      (node (ref "J2") (pin "39") (pinfunction "39_39") (pintype "unspecified"))
      (node (ref "P4") (pin "8") (pinfunction "8_8") (pintype "unspecified"))
      (node (ref "U4") (pin "7") (pinfunction "Y7_7") (pintype "unspecified"))
    )
    (net (code "55") (name "DTR-A") (class "Default")
      (node (ref "H7") (pin "2") (pinfunction "2_2") (pintype "unspecified"))
      (node (ref "U6") (pin "16") (pinfunction "DTR/REQA_16") (pintype "output"))
    )
    (net (code "56") (name "DTR-B") (class "Default")
      (node (ref "H8") (pin "2") (pinfunction "2_2") (pintype "unspecified"))
      (node (ref "U6") (pin "24") (pinfunction "DTR/REQB_24") (pintype "output"))
    )
    (net (code "57") (name "EN_INA") (class "Default")
      (node (ref "U14") (pin "13") (pinfunction "4Y_13") (pintype "unspecified"))
      (node (ref "U8") (pin "3") (pinfunction "2A_3") (pintype "unspecified"))
    )
    (net (code "58") (name "EN_INA#") (class "Default")
      (node (ref "U15") (pin "1") (pinfunction "1OE#_1") (pintype "unspecified"))
      (node (ref "U15") (pin "19") (pinfunction "2OE#_19") (pintype "unspecified"))
      (node (ref "U8") (pin "4") (pinfunction "2Y_4") (pintype "unspecified"))
    )
    (net (code "59") (name "EN_INB") (class "Default")
      (node (ref "U14") (pin "10") (pinfunction "3Y_10") (pintype "unspecified"))
      (node (ref "U8") (pin "13") (pinfunction "6A_13") (pintype "unspecified"))
    )
    (net (code "60") (name "EN_INB#") (class "Default")
      (node (ref "U16") (pin "1") (pinfunction "1OE#_1") (pintype "unspecified"))
      (node (ref "U16") (pin "19") (pinfunction "2OE#_19") (pintype "unspecified"))
      (node (ref "U8") (pin "12") (pinfunction "6Y_12") (pintype "unspecified"))
    )
    (net (code "61") (name "EN_OUT_A") (class "Default")
      (node (ref "U12") (pin "11") (pinfunction "CP_11") (pintype "unspecified"))
      (node (ref "U14") (pin "1") (pinfunction "1Y_1") (pintype "unspecified"))
    )
    (net (code "62") (name "EN_OUT_B") (class "Default")
      (node (ref "U13") (pin "11") (pinfunction "CP_11") (pintype "unspecified"))
      (node (ref "U14") (pin "4") (pinfunction "2Y_4") (pintype "unspecified"))
    )
    (net (code "63") (name "EN_RAM") (class "Default")
      (node (ref "U10") (pin "6") (pinfunction "2Y_6") (pintype "unspecified"))
      (node (ref "U3") (pin "20") (pinfunction "CE#_20") (pintype "unspecified"))
    )
    (net (code "64") (name "EN_ROM") (class "Default")
      (node (ref "U10") (pin "3") (pinfunction "1Y_3") (pintype "unspecified"))
      (node (ref "U2") (pin "20") (pinfunction "CE#_20") (pintype "unspecified"))
    )
    (net (code "65") (name "GND") (class "Default")
      (node (ref "C1") (pin "2") (pinfunction "2_2") (pintype "unspecified"))
      (node (ref "C10") (pin "2") (pinfunction "2_2") (pintype "unspecified"))
      (node (ref "C11") (pin "2") (pinfunction "2_2") (pintype "unspecified"))
      (node (ref "C12") (pin "2") (pinfunction "2_2") (pintype "unspecified"))
      (node (ref "C13") (pin "2") (pinfunction "2_2") (pintype "unspecified"))
      (node (ref "C14") (pin "2") (pinfunction "2_2") (pintype "unspecified"))
      (node (ref "C15") (pin "2") (pinfunction "2_2") (pintype "unspecified"))
      (node (ref "C16") (pin "2") (pinfunction "2_2") (pintype "unspecified"))
      (node (ref "C17") (pin "2") (pinfunction "2_2") (pintype "unspecified"))
      (node (ref "C18") (pin "2") (pinfunction "2_2") (pintype "unspecified"))
      (node (ref "C19") (pin "1") (pinfunction "1_1") (pintype "unspecified"))
      (node (ref "C2") (pin "2") (pinfunction "2_2") (pintype "unspecified"))
      (node (ref "C20") (pin "1") (pinfunction "1_1") (pintype "unspecified"))
      (node (ref "C21") (pin "2") (pinfunction "2_2") (pintype "unspecified"))
      (node (ref "C22") (pin "2") (pinfunction "2_2") (pintype "unspecified"))
      (node (ref "C23") (pin "2") (pinfunction "2_2") (pintype "input"))
      (node (ref "C3") (pin "2") (pinfunction "2_2") (pintype "unspecified"))
      (node (ref "C4") (pin "2") (pinfunction "2_2") (pintype "unspecified"))
      (node (ref "C5") (pin "2") (pinfunction "2_2") (pintype "unspecified"))
      (node (ref "C6") (pin "2") (pinfunction "2_2") (pintype "unspecified"))
      (node (ref "C8") (pin "2") (pinfunction "2_2") (pintype "unspecified"))
      (node (ref "C9") (pin "2") (pinfunction "2_2") (pintype "unspecified"))
      (node (ref "DC1") (pin "2") (pinfunction "2_2") (pintype "unspecified"))
      (node (ref "DC1") (pin "3") (pinfunction "3_3") (pintype "unspecified"))
      (node (ref "H2") (pin "35") (pinfunction "35_35") (pintype "unspecified"))
      (node (ref "H2") (pin "36") (pinfunction "36_36") (pintype "unspecified"))
      (node (ref "H7") (pin "6") (pinfunction "6_6") (pintype "unspecified"))
      (node (ref "H8") (pin "6") (pinfunction "6_6") (pintype "unspecified"))
      (node (ref "J1") (pin "18") (pinfunction "18_18") (pintype "unspecified"))
      (node (ref "J2") (pin "18") (pinfunction "18_18") (pintype "unspecified"))
      (node (ref "J6") (pin "39") (pinfunction "39_39") (pintype "unspecified"))
      (node (ref "LCD1") (pin "1") (pinfunction "GND_1") (pintype "unspecified"))
      (node (ref "LCD1") (pin "16") (pinfunction "LED-_16") (pintype "unspecified"))
      (node (ref "LCD1") (pin "5") (pinfunction "RW_5") (pintype "unspecified"))
      (node (ref "LED1") (pin "2") (pinfunction "2_2") (pintype "unspecified"))
      (node (ref "P1") (pin "10") (pinfunction "10_10") (pintype "unspecified"))
      (node (ref "P2") (pin "10") (pinfunction "10_10") (pintype "unspecified"))
      (node (ref "P3") (pin "6") (pinfunction "6_6") (pintype "unspecified"))
      (node (ref "P4") (pin "10") (pinfunction "10_10") (pintype "unspecified"))
      (node (ref "P5") (pin "10") (pinfunction "10_10") (pintype "unspecified"))
      (node (ref "P6") (pin "10") (pinfunction "10_10") (pintype "unspecified"))
      (node (ref "P7") (pin "10") (pinfunction "10_10") (pintype "unspecified"))
      (node (ref "P8") (pin "10") (pinfunction "10_10") (pintype "unspecified"))
      (node (ref "Q1") (pin "3") (pinfunction "E_3") (pintype "input"))
      (node (ref "R10") (pin "1") (pinfunction "1_1") (pintype "unspecified"))
      (node (ref "R26") (pin "1") (pinfunction "1_1") (pintype "unspecified"))
      (node (ref "R9") (pin "1") (pinfunction "1_1") (pintype "unspecified"))
      (node (ref "RP1") (pin "1") (pinfunction "1_1") (pintype "input"))
      (node (ref "RT1") (pin "2") (pinfunction "GND_2") (pintype "unspecified"))
      (node (ref "U1") (pin "29") (pinfunction "GND_29") (pintype "unspecified"))
      (node (ref "U10") (pin "10") (pinfunction "3B_10") (pintype "unspecified"))
      (node (ref "U10") (pin "7") (pinfunction "GND_7") (pintype "unspecified"))
      (node (ref "U10") (pin "9") (pinfunction "3A_9") (pintype "unspecified"))
      (node (ref "U11") (pin "11") (pinfunction "2CLK_11") (pintype "unspecified"))
      (node (ref "U11") (pin "12") (pinfunction "2D_12") (pintype "unspecified"))
      (node (ref "U11") (pin "7") (pinfunction "GND_7") (pintype "unspecified"))
      (node (ref "U12") (pin "1") (pinfunction "OE#_1") (pintype "unspecified"))
      (node (ref "U12") (pin "10") (pinfunction "GND_10") (pintype "unspecified"))
      (node (ref "U13") (pin "1") (pinfunction "OE#_1") (pintype "unspecified"))
      (node (ref "U13") (pin "10") (pinfunction "GND_10") (pintype "unspecified"))
      (node (ref "U14") (pin "7") (pinfunction "GND_7") (pintype "unspecified"))
      (node (ref "U15") (pin "10") (pinfunction "GND_10") (pintype "unspecified"))
      (node (ref "U16") (pin "10") (pinfunction "GND_10") (pintype "unspecified"))
      (node (ref "U2") (pin "14") (pinfunction "GND_14") (pintype "unspecified"))
      (node (ref "U3") (pin "14") (pinfunction "GND_14") (pintype "unspecified"))
      (node (ref "U4") (pin "5") (pinfunction "G2B#_5") (pintype "unspecified"))
      (node (ref "U4") (pin "8") (pinfunction "GND_8") (pintype "unspecified"))
      (node (ref "U5") (pin "7") (pinfunction "GND_7") (pintype "unspecified"))
      (node (ref "U6") (pin "18") (pinfunction "CTSA_18") (pintype "input"))
      (node (ref "U6") (pin "19") (pinfunction "DCDA_19") (pintype "input"))
      (node (ref "U6") (pin "21") (pinfunction "DCDB_21") (pintype "input"))
      (node (ref "U6") (pin "22") (pinfunction "CTSB_22") (pintype "input"))
      (node (ref "U6") (pin "31") (pinfunction "GND_31") (pintype "unspecified"))
      (node (ref "U8") (pin "7") (pinfunction "GND_7") (pintype "unspecified"))
      (node (ref "U9") (pin "11") (pinfunction "5A_11") (pintype "unspecified"))
      (node (ref "U9") (pin "5") (pinfunction "3A_5") (pintype "unspecified"))
      (node (ref "U9") (pin "7") (pinfunction "GND_7") (pintype "unspecified"))
      (node (ref "U9") (pin "9") (pinfunction "4A_9") (pintype "unspecified"))
      (node (ref "X5") (pin "2") (pinfunction "2_2") (pintype "unspecified"))
    )
    (net (code "66") (name "HALT") (class "Default")
      (node (ref "J6") (pin "37") (pinfunction "37_37") (pintype "unspecified"))
      (node (ref "U1") (pin "18") (pinfunction "HALT#_18") (pintype "unspecified"))
      (node (ref "X4") (pin "1") (pinfunction "1_1") (pintype "unspecified"))
    )
    (net (code "67") (name "IA0") (class "Default")
      (node (ref "P7") (pin "2") (pinfunction "2_2") (pintype "unspecified"))
      (node (ref "U15") (pin "2") (pinfunction "1A1_2") (pintype "unspecified"))
    )
    (net (code "68") (name "IA1") (class "Default")
      (node (ref "P7") (pin "3") (pinfunction "3_3") (pintype "unspecified"))
      (node (ref "U15") (pin "4") (pinfunction "1A2_4") (pintype "unspecified"))
    )
    (net (code "69") (name "IA2") (class "Default")
      (node (ref "P7") (pin "4") (pinfunction "4_4") (pintype "unspecified"))
      (node (ref "U15") (pin "6") (pinfunction "1A3_6") (pintype "unspecified"))
    )
    (net (code "70") (name "IA3") (class "Default")
      (node (ref "P7") (pin "5") (pinfunction "5_5") (pintype "unspecified"))
      (node (ref "U15") (pin "8") (pinfunction "1A4_8") (pintype "unspecified"))
    )
    (net (code "71") (name "IA4") (class "Default")
      (node (ref "P7") (pin "6") (pinfunction "6_6") (pintype "unspecified"))
      (node (ref "U15") (pin "11") (pinfunction "2A1_11") (pintype "unspecified"))
    )
    (net (code "72") (name "IA5") (class "Default")
      (node (ref "P7") (pin "7") (pinfunction "7_7") (pintype "unspecified"))
      (node (ref "U15") (pin "13") (pinfunction "2A2_13") (pintype "unspecified"))
    )
    (net (code "73") (name "IA6") (class "Default")
      (node (ref "P7") (pin "8") (pinfunction "8_8") (pintype "unspecified"))
      (node (ref "U15") (pin "15") (pinfunction "2A3_15") (pintype "unspecified"))
    )
    (net (code "74") (name "IA7") (class "Default")
      (node (ref "P7") (pin "9") (pinfunction "9_9") (pintype "unspecified"))
      (node (ref "U15") (pin "17") (pinfunction "2A4_17") (pintype "unspecified"))
    )
    (net (code "75") (name "IB0") (class "Default")
      (node (ref "P8") (pin "2") (pinfunction "2_2") (pintype "unspecified"))
      (node (ref "U16") (pin "2") (pinfunction "1A1_2") (pintype "unspecified"))
    )
    (net (code "76") (name "IB1") (class "Default")
      (node (ref "P8") (pin "3") (pinfunction "3_3") (pintype "unspecified"))
      (node (ref "U16") (pin "4") (pinfunction "1A2_4") (pintype "unspecified"))
    )
    (net (code "77") (name "IB2") (class "Default")
      (node (ref "P8") (pin "4") (pinfunction "4_4") (pintype "unspecified"))
      (node (ref "U16") (pin "6") (pinfunction "1A3_6") (pintype "unspecified"))
    )
    (net (code "78") (name "IB3") (class "Default")
      (node (ref "P8") (pin "5") (pinfunction "5_5") (pintype "unspecified"))
      (node (ref "U16") (pin "8") (pinfunction "1A4_8") (pintype "unspecified"))
    )
    (net (code "79") (name "IB4") (class "Default")
      (node (ref "P8") (pin "6") (pinfunction "6_6") (pintype "unspecified"))
      (node (ref "U16") (pin "11") (pinfunction "2A1_11") (pintype "unspecified"))
    )
    (net (code "80") (name "IB5") (class "Default")
      (node (ref "P8") (pin "7") (pinfunction "7_7") (pintype "unspecified"))
      (node (ref "U16") (pin "13") (pinfunction "2A2_13") (pintype "unspecified"))
    )
    (net (code "81") (name "IB6") (class "Default")
      (node (ref "P8") (pin "8") (pinfunction "8_8") (pintype "unspecified"))
      (node (ref "U16") (pin "15") (pinfunction "2A3_15") (pintype "unspecified"))
    )
    (net (code "82") (name "IB7") (class "Default")
      (node (ref "P8") (pin "9") (pinfunction "9_9") (pintype "unspecified"))
      (node (ref "U16") (pin "17") (pinfunction "2A4_17") (pintype "unspecified"))
    )
    (net (code "83") (name "IEI-CIO") (class "Default")
      (node (ref "U5") (pin "17") (pinfunction "IEI_17") (pintype "unspecified"))
      (node (ref "U6") (pin "6") (pinfunction "IEO_6") (pintype "output"))
    )
    (net (code "84") (name "IEO-SCC") (class "Default")
      (node (ref "R13") (pin "2") (pinfunction "2_2") (pintype "unspecified"))
      (node (ref "U6") (pin "7") (pinfunction "IEI_7") (pintype "input"))
    )
    (net (code "85") (name "INT") (class "Default")
      (node (ref "H3") (pin "2") (pinfunction "2_2") (pintype "unspecified"))
      (node (ref "J1") (pin "22") (pinfunction "22_22") (pintype "unspecified"))
      (node (ref "J2") (pin "22") (pinfunction "22_22") (pintype "unspecified"))
      (node (ref "J6") (pin "33") (pinfunction "33_33") (pintype "unspecified"))
      (node (ref "RN1") (pin "2") (pinfunction "2_2") (pintype "input"))
      (node (ref "U1") (pin "16") (pinfunction "INT#_16") (pintype "unspecified"))
      (node (ref "U5") (pin "24") (pinfunction "INT#_24") (pintype "unspecified"))
      (node (ref "U6") (pin "5") (pinfunction "INT_5") (pintype "unspecified"))
    )
    (net (code "86") (name "INTACK") (class "Default")
      (node (ref "U5") (pin "25") (pinfunction "INTACK#_25") (pintype "unspecified"))
      (node (ref "U6") (pin "8") (pinfunction "INTACK_8") (pintype "input"))
    )
    (net (code "87") (name "IORQ") (class "Default")
      (node (ref "H2") (pin "28") (pinfunction "28_28") (pintype "unspecified"))
      (node (ref "J1") (pin "26") (pinfunction "26_26") (pintype "unspecified"))
      (node (ref "J2") (pin "26") (pinfunction "26_26") (pintype "unspecified"))
      (node (ref "J6") (pin "25") (pinfunction "25_25") (pintype "unspecified"))
      (node (ref "RN1") (pin "5") (pinfunction "5_5") (pintype "input"))
      (node (ref "U1") (pin "20") (pinfunction "IORQ#_20") (pintype "unspecified"))
      (node (ref "U4") (pin "4") (pinfunction "G2A#_4") (pintype "unspecified"))
    )
    (net (code "88") (name "M1") (class "Default")
      (node (ref "H2") (pin "34") (pinfunction "34_34") (pintype "unspecified"))
      (node (ref "J1") (pin "19") (pinfunction "19_19") (pintype "unspecified"))
      (node (ref "J2") (pin "19") (pinfunction "19_19") (pintype "unspecified"))
      (node (ref "J6") (pin "38") (pinfunction "38_38") (pintype "unspecified"))
      (node (ref "U1") (pin "27") (pinfunction "M1#_27") (pintype "unspecified"))
      (node (ref "U4") (pin "6") (pinfunction "G1_6") (pintype "unspecified"))
    )
    (net (code "89") (name "MREQ") (class "Default")
      (node (ref "H2") (pin "26") (pinfunction "26_26") (pintype "unspecified"))
      (node (ref "J1") (pin "23") (pinfunction "23_23") (pintype "unspecified"))
      (node (ref "J2") (pin "23") (pinfunction "23_23") (pintype "unspecified"))
      (node (ref "J6") (pin "27") (pinfunction "27_27") (pintype "unspecified"))
      (node (ref "RN1") (pin "4") (pinfunction "4_4") (pintype "input"))
      (node (ref "U1") (pin "19") (pinfunction "MREQ#_19") (pintype "unspecified"))
      (node (ref "U10") (pin "1") (pinfunction "1A_1") (pintype "unspecified"))
      (node (ref "U10") (pin "4") (pinfunction "2A_4") (pintype "unspecified"))
    )
    (net (code "90") (name "NMI") (class "Default")
      (node (ref "H3") (pin "1") (pinfunction "1_1") (pintype "unspecified"))
      (node (ref "J6") (pin "35") (pinfunction "35_35") (pintype "unspecified"))
      (node (ref "RN1") (pin "3") (pinfunction "3_3") (pintype "input"))
      (node (ref "U1") (pin "17") (pinfunction "NMI#_17") (pintype "unspecified"))
    )
    (net (code "91") (name "Net-(H6-Pad1)") (class "Default")
      (node (ref "H6") (pin "1") (pinfunction "1_1") (pintype "unspecified"))
      (node (ref "R17") (pin "2") (pinfunction "2_2") (pintype "unspecified"))
    )
    (net (code "92") (name "Net-(LCD1-LED+)") (class "Default")
      (node (ref "LCD1") (pin "15") (pinfunction "LED+_15") (pintype "unspecified"))
      (node (ref "R27") (pin "1") (pinfunction "1_1") (pintype "unspecified"))
    )
    (net (code "93") (name "Net-(LCD1-Vo)") (class "Default")
      (node (ref "LCD1") (pin "3") (pinfunction "Vo_3") (pintype "unspecified"))
      (node (ref "RP1") (pin "2") (pinfunction "2_2") (pintype "input"))
    )
    (net (code "94") (name "Net-(LED1-Pad1)") (class "Default")
      (node (ref "LED1") (pin "1") (pinfunction "1_1") (pintype "unspecified"))
      (node (ref "R1") (pin "1") (pinfunction "1_1") (pintype "input"))
    )
    (net (code "95") (name "Net-(LED2-Pad1)") (class "Default")
      (node (ref "LED2") (pin "1") (pinfunction "1_1") (pintype "unspecified"))
      (node (ref "R16") (pin "1") (pinfunction "1_1") (pintype "unspecified"))
    )
    (net (code "96") (name "Net-(Q1-B)") (class "Default")
      (node (ref "Q1") (pin "2") (pinfunction "B_2") (pintype "input"))
      (node (ref "R17") (pin "1") (pinfunction "1_1") (pintype "unspecified"))
    )
    (net (code "97") (name "Net-(Q1-C)") (class "Default")
      (node (ref "LED2") (pin "2") (pinfunction "2_2") (pintype "unspecified"))
      (node (ref "Q1") (pin "1") (pinfunction "C_1") (pintype "input"))
    )
    (net (code "98") (name "Net-(RT1-INPUT)") (class "Default")
      (node (ref "C23") (pin "1") (pinfunction "1_1") (pintype "input"))
      (node (ref "DC1") (pin "1") (pinfunction "1_1") (pintype "unspecified"))
      (node (ref "RT1") (pin "1") (pinfunction "INPUT_1") (pintype "unspecified"))
      (node (ref "X5") (pin "1") (pinfunction "1_1") (pintype "unspecified"))
    )
    (net (code "99") (name "Net-(RT1-OUTPUT)") (class "Default")
      (node (ref "C21") (pin "1") (pinfunction "1_1") (pintype "unspecified"))
      (node (ref "C22") (pin "1") (pinfunction "1_1") (pintype "unspecified"))
      (node (ref "RT1") (pin "3") (pinfunction "OUTPUT_3") (pintype "unspecified"))
      (node (ref "X6") (pin "4") (pinfunction "4_4") (pintype "unspecified"))
    )
    (net (code "100") (name "Net-(SW1-A)") (class "Default")
      (node (ref "R10") (pin "2") (pinfunction "2_2") (pintype "unspecified"))
      (node (ref "SW1") (pin "1") (pinfunction "A_1") (pintype "unspecified"))
    )
    (net (code "101") (name "Net-(SW1-D)") (class "Default")
      (node (ref "C18") (pin "1") (pinfunction "1_1") (pintype "unspecified"))
      (node (ref "R11") (pin "1") (pinfunction "1_1") (pintype "unspecified"))
      (node (ref "SW1") (pin "4") (pinfunction "D_4") (pintype "unspecified"))
      (node (ref "U9") (pin "3") (pinfunction "2A_3") (pintype "unspecified"))
    )
    (net (code "102") (name "Net-(SW4-A)") (class "Default")
      (node (ref "R9") (pin "2") (pinfunction "2_2") (pintype "unspecified"))
      (node (ref "SW4") (pin "1") (pinfunction "A_1") (pintype "unspecified"))
    )
    (net (code "103") (name "Net-(SW4-D)") (class "Default")
      (node (ref "C17") (pin "1") (pinfunction "1_1") (pintype "unspecified"))
      (node (ref "R12") (pin "1") (pinfunction "1_1") (pintype "unspecified"))
      (node (ref "SW4") (pin "4") (pinfunction "D_4") (pintype "unspecified"))
      (node (ref "U9") (pin "1") (pinfunction "1A_1") (pintype "unspecified"))
    )
    (net (code "104") (name "Net-(U6-RTSA)") (class "Default")
      (node (ref "R20") (pin "1") (pinfunction "1_1") (pintype "unspecified"))
      (node (ref "U6") (pin "17") (pinfunction "RTSA_17") (pintype "output"))
    )
    (net (code "105") (name "Net-(U6-RTSB)") (class "Default")
      (node (ref "R21") (pin "1") (pinfunction "1_1") (pintype "unspecified"))
      (node (ref "U6") (pin "23") (pinfunction "RTSB_23") (pintype "output"))
    )
    (net (code "106") (name "Net-(U6-RXDA)") (class "Default")
      (node (ref "R18") (pin "1") (pinfunction "1_1") (pintype "unspecified"))
      (node (ref "U6") (pin "13") (pinfunction "RXDA_13") (pintype "input"))
    )
    (net (code "107") (name "Net-(U6-RXDB)") (class "Default")
      (node (ref "R23") (pin "1") (pinfunction "1_1") (pintype "unspecified"))
      (node (ref "U6") (pin "27") (pinfunction "RXDB_27") (pintype "input"))
    )
    (net (code "108") (name "Net-(U6-SYNCA)") (class "Default")
      (node (ref "R24") (pin "1") (pinfunction "1_1") (pintype "unspecified"))
      (node (ref "U6") (pin "11") (pinfunction "SYNCA_11") (pintype "bidirectional"))
    )
    (net (code "109") (name "Net-(U6-SYNCB)") (class "Default")
      (node (ref "R25") (pin "1") (pinfunction "1_1") (pintype "unspecified"))
      (node (ref "U6") (pin "29") (pinfunction "SYNCB_29") (pintype "bidirectional"))
    )
    (net (code "110") (name "Net-(U6-TXDA)") (class "Default")
      (node (ref "R19") (pin "1") (pinfunction "1_1") (pintype "unspecified"))
      (node (ref "U6") (pin "15") (pinfunction "TXDA_15") (pintype "output"))
    )
    (net (code "111") (name "Net-(U6-TXDB)") (class "Default")
      (node (ref "R22") (pin "1") (pinfunction "1_1") (pintype "unspecified"))
      (node (ref "U6") (pin "25") (pinfunction "TXDB_25") (pintype "output"))
    )
    (net (code "112") (name "Net-(U11-1D)") (class "Default")
      (node (ref "U11") (pin "2") (pinfunction "1D_2") (pintype "unspecified"))
      (node (ref "U11") (pin "6") (pinfunction "1Q#_6") (pintype "unspecified"))
    )
    (net (code "113") (name "Net-(XTAL1-OSC2)") (class "Default")
      (node (ref "C19") (pin "2") (pinfunction "2_2") (pintype "unspecified"))
      (node (ref "R15") (pin "1") (pinfunction "1_1") (pintype "unspecified"))
      (node (ref "XTAL1") (pin "2") (pinfunction "OSC2_2") (pintype "unspecified"))
    )
    (net (code "114") (name "OA0") (class "Default")
      (node (ref "P5") (pin "2") (pinfunction "2_2") (pintype "unspecified"))
      (node (ref "U12") (pin "19") (pinfunction "Q0_19") (pintype "unspecified"))
    )
    (net (code "115") (name "OA1") (class "Default")
      (node (ref "P5") (pin "3") (pinfunction "3_3") (pintype "unspecified"))
      (node (ref "U12") (pin "18") (pinfunction "Q1_18") (pintype "unspecified"))
    )
    (net (code "116") (name "OA2") (class "Default")
      (node (ref "P5") (pin "4") (pinfunction "4_4") (pintype "unspecified"))
      (node (ref "U12") (pin "17") (pinfunction "Q2_17") (pintype "unspecified"))
    )
    (net (code "117") (name "OA3") (class "Default")
      (node (ref "P5") (pin "5") (pinfunction "5_5") (pintype "unspecified"))
      (node (ref "U12") (pin "16") (pinfunction "Q3_16") (pintype "unspecified"))
    )
    (net (code "118") (name "OA4") (class "Default")
      (node (ref "P5") (pin "6") (pinfunction "6_6") (pintype "unspecified"))
      (node (ref "U12") (pin "15") (pinfunction "Q4_15") (pintype "unspecified"))
    )
    (net (code "119") (name "OA5") (class "Default")
      (node (ref "P5") (pin "7") (pinfunction "7_7") (pintype "unspecified"))
      (node (ref "U12") (pin "14") (pinfunction "Q5_14") (pintype "unspecified"))
    )
    (net (code "120") (name "OA6") (class "Default")
      (node (ref "P5") (pin "8") (pinfunction "8_8") (pintype "unspecified"))
      (node (ref "U12") (pin "13") (pinfunction "Q6_13") (pintype "unspecified"))
    )
    (net (code "121") (name "OA7") (class "Default")
      (node (ref "P5") (pin "9") (pinfunction "9_9") (pintype "unspecified"))
      (node (ref "U12") (pin "12") (pinfunction "Q7_12") (pintype "unspecified"))
    )
    (net (code "122") (name "OB0") (class "Default")
      (node (ref "P6") (pin "2") (pinfunction "2_2") (pintype "unspecified"))
      (node (ref "U13") (pin "19") (pinfunction "Q0_19") (pintype "unspecified"))
    )
    (net (code "123") (name "OB1") (class "Default")
      (node (ref "P6") (pin "3") (pinfunction "3_3") (pintype "unspecified"))
      (node (ref "U13") (pin "18") (pinfunction "Q1_18") (pintype "unspecified"))
    )
    (net (code "124") (name "OB2") (class "Default")
      (node (ref "LCD1") (pin "4") (pinfunction "RS_4") (pintype "unspecified"))
      (node (ref "P6") (pin "4") (pinfunction "4_4") (pintype "unspecified"))
      (node (ref "U13") (pin "17") (pinfunction "Q2_17") (pintype "unspecified"))
    )
    (net (code "125") (name "OB3") (class "Default")
      (node (ref "LCD1") (pin "6") (pinfunction "E_6") (pintype "unspecified"))
      (node (ref "P6") (pin "5") (pinfunction "5_5") (pintype "unspecified"))
      (node (ref "U13") (pin "16") (pinfunction "Q3_16") (pintype "unspecified"))
    )
    (net (code "126") (name "OB4") (class "Default")
      (node (ref "LCD1") (pin "11") (pinfunction "DB4_11") (pintype "unspecified"))
      (node (ref "P6") (pin "6") (pinfunction "6_6") (pintype "unspecified"))
      (node (ref "U13") (pin "15") (pinfunction "Q4_15") (pintype "unspecified"))
    )
    (net (code "127") (name "OB5") (class "Default")
      (node (ref "LCD1") (pin "12") (pinfunction "DB5_12") (pintype "unspecified"))
      (node (ref "P6") (pin "7") (pinfunction "7_7") (pintype "unspecified"))
      (node (ref "U13") (pin "14") (pinfunction "Q5_14") (pintype "unspecified"))
    )
    (net (code "128") (name "OB6") (class "Default")
      (node (ref "LCD1") (pin "13") (pinfunction "DB6_13") (pintype "unspecified"))
      (node (ref "P6") (pin "8") (pinfunction "8_8") (pintype "unspecified"))
      (node (ref "U13") (pin "13") (pinfunction "Q6_13") (pintype "unspecified"))
    )
    (net (code "129") (name "OB7") (class "Default")
      (node (ref "LCD1") (pin "14") (pinfunction "DB7_14") (pintype "unspecified"))
      (node (ref "P6") (pin "9") (pinfunction "9_9") (pintype "unspecified"))
      (node (ref "U13") (pin "12") (pinfunction "Q7_12") (pintype "unspecified"))
    )
    (net (code "130") (name "PA0") (class "Default")
      (node (ref "P1") (pin "2") (pinfunction "2_2") (pintype "unspecified"))
      (node (ref "U5") (pin "33") (pinfunction "PA0_33") (pintype "unspecified"))
    )
    (net (code "131") (name "PA1") (class "Default")
      (node (ref "P1") (pin "3") (pinfunction "3_3") (pintype "unspecified"))
      (node (ref "U5") (pin "32") (pinfunction "PA1_32") (pintype "unspecified"))
    )
    (net (code "132") (name "PA2") (class "Default")
      (node (ref "P1") (pin "4") (pinfunction "4_4") (pintype "unspecified"))
      (node (ref "U5") (pin "31") (pinfunction "PA2_31") (pintype "unspecified"))
    )
    (net (code "133") (name "PA3") (class "Default")
      (node (ref "P1") (pin "5") (pinfunction "5_5") (pintype "unspecified"))
      (node (ref "U5") (pin "30") (pinfunction "PA3_30") (pintype "unspecified"))
    )
    (net (code "134") (name "PA4") (class "Default")
      (node (ref "P1") (pin "6") (pinfunction "6_6") (pintype "unspecified"))
      (node (ref "U5") (pin "29") (pinfunction "PA4_29") (pintype "unspecified"))
    )
    (net (code "135") (name "PA5") (class "Default")
      (node (ref "P1") (pin "7") (pinfunction "7_7") (pintype "unspecified"))
      (node (ref "U5") (pin "28") (pinfunction "PA5_28") (pintype "unspecified"))
    )
    (net (code "136") (name "PA6") (class "Default")
      (node (ref "P1") (pin "8") (pinfunction "8_8") (pintype "unspecified"))
      (node (ref "U5") (pin "27") (pinfunction "PA6_27") (pintype "unspecified"))
    )
    (net (code "137") (name "PA7") (class "Default")
      (node (ref "P1") (pin "9") (pinfunction "9_9") (pintype "unspecified"))
      (node (ref "U5") (pin "26") (pinfunction "PA7_26") (pintype "unspecified"))
    )
    (net (code "138") (name "PB0") (class "Default")
      (node (ref "H6") (pin "2") (pinfunction "2_2") (pintype "unspecified"))
      (node (ref "P2") (pin "2") (pinfunction "2_2") (pintype "unspecified"))
      (node (ref "U5") (pin "8") (pinfunction "PB0_8") (pintype "unspecified"))
    )
    (net (code "139") (name "PB1") (class "Default")
      (node (ref "P2") (pin "3") (pinfunction "3_3") (pintype "unspecified"))
      (node (ref "U5") (pin "9") (pinfunction "PB1_9") (pintype "unspecified"))
    )
    (net (code "140") (name "PB2") (class "Default")
      (node (ref "P2") (pin "4") (pinfunction "4_4") (pintype "unspecified"))
      (node (ref "U5") (pin "10") (pinfunction "PB2_10") (pintype "unspecified"))
    )
    (net (code "141") (name "PB3") (class "Default")
      (node (ref "P2") (pin "5") (pinfunction "5_5") (pintype "unspecified"))
      (node (ref "U5") (pin "11") (pinfunction "PB3_11") (pintype "unspecified"))
    )
    (net (code "142") (name "PB4") (class "Default")
      (node (ref "P2") (pin "6") (pinfunction "6_6") (pintype "unspecified"))
      (node (ref "U5") (pin "12") (pinfunction "PB4_12") (pintype "unspecified"))
    )
    (net (code "143") (name "PB5") (class "Default")
      (node (ref "P2") (pin "7") (pinfunction "7_7") (pintype "unspecified"))
      (node (ref "U5") (pin "13") (pinfunction "PB5_13") (pintype "unspecified"))
    )
    (net (code "144") (name "PB6") (class "Default")
      (node (ref "P2") (pin "8") (pinfunction "8_8") (pintype "unspecified"))
      (node (ref "U5") (pin "14") (pinfunction "PB6_14") (pintype "unspecified"))
    )
    (net (code "145") (name "PB7") (class "Default")
      (node (ref "P2") (pin "9") (pinfunction "9_9") (pintype "unspecified"))
      (node (ref "U5") (pin "15") (pinfunction "PB7_15") (pintype "unspecified"))
    )
    (net (code "146") (name "PC0") (class "Default")
      (node (ref "P3") (pin "2") (pinfunction "2_2") (pintype "unspecified"))
      (node (ref "U5") (pin "19") (pinfunction "PC0_19") (pintype "unspecified"))
    )
    (net (code "147") (name "PC1") (class "Default")
      (node (ref "P3") (pin "3") (pinfunction "3_3") (pintype "unspecified"))
      (node (ref "U5") (pin "20") (pinfunction "PC1_20") (pintype "unspecified"))
    )
    (net (code "148") (name "PC2") (class "Default")
      (node (ref "P3") (pin "4") (pinfunction "4_4") (pintype "unspecified"))
      (node (ref "U5") (pin "21") (pinfunction "PC2_21") (pintype "unspecified"))
    )
    (net (code "149") (name "PC3") (class "Default")
      (node (ref "P3") (pin "5") (pinfunction "5_5") (pintype "unspecified"))
      (node (ref "U5") (pin "22") (pinfunction "PC3_22") (pintype "unspecified"))
    )
    (net (code "150") (name "RD") (class "Default")
      (node (ref "H2") (pin "30") (pinfunction "30_30") (pintype "unspecified"))
      (node (ref "J1") (pin "25") (pinfunction "25_25") (pintype "unspecified"))
      (node (ref "J2") (pin "25") (pinfunction "25_25") (pintype "unspecified"))
      (node (ref "J6") (pin "23") (pinfunction "23_23") (pintype "unspecified"))
      (node (ref "RN1") (pin "9") (pinfunction "9_9") (pintype "input"))
      (node (ref "U1") (pin "21") (pinfunction "RD#_21") (pintype "unspecified"))
      (node (ref "U14") (pin "12") (pinfunction "4B_12") (pintype "unspecified"))
      (node (ref "U14") (pin "9") (pinfunction "3B_9") (pintype "unspecified"))
      (node (ref "U2") (pin "22") (pinfunction "OE#_22") (pintype "unspecified"))
      (node (ref "U3") (pin "22") (pinfunction "OE#_22") (pintype "unspecified"))
      (node (ref "U5") (pin "5") (pinfunction "RD#_5") (pintype "unspecified"))
      (node (ref "U6") (pin "36") (pinfunction "RD_36") (pintype "input"))
    )
    (net (code "151") (name "RFSH") (class "Default")
      (node (ref "H2") (pin "24") (pinfunction "24_24") (pintype "unspecified"))
      (node (ref "J6") (pin "29") (pinfunction "29_29") (pintype "unspecified"))
      (node (ref "U1") (pin "28") (pinfunction "RFSH#_28") (pintype "unspecified"))
    )
    (net (code "152") (name "RST") (class "Default")
      (node (ref "J1") (pin "20") (pinfunction "20_20") (pintype "unspecified"))
      (node (ref "J2") (pin "20") (pinfunction "20_20") (pintype "unspecified"))
      (node (ref "J6") (pin "36") (pinfunction "36_36") (pintype "unspecified"))
      (node (ref "U1") (pin "26") (pinfunction "RESET#_26") (pintype "unspecified"))
      (node (ref "U8") (pin "6") (pinfunction "3Y_6") (pintype "unspecified"))
    )
    (net (code "153") (name "RST-ARD") (class "Default")
      (node (ref "H4") (pin "1") (pinfunction "1_1") (pintype "unspecified"))
      (node (ref "R26") (pin "2") (pinfunction "2_2") (pintype "unspecified"))
      (node (ref "U10") (pin "12") (pinfunction "4A_12") (pintype "unspecified"))
    )
    (net (code "154") (name "RX") (class "Default")
      (node (ref "H7") (pin "3") (pinfunction "3_3") (pintype "unspecified"))
      (node (ref "J1") (pin "36") (pinfunction "36_36") (pintype "unspecified"))
      (node (ref "J2") (pin "36") (pinfunction "36_36") (pintype "unspecified"))
      (node (ref "R19") (pin "2") (pinfunction "2_2") (pintype "unspecified"))
    )
    (net (code "155") (name "RX-B") (class "Default")
      (node (ref "H8") (pin "3") (pinfunction "3_3") (pintype "unspecified"))
      (node (ref "R22") (pin "2") (pinfunction "2_2") (pintype "unspecified"))
    )
    (net (code "156") (name "TX") (class "Default")
      (node (ref "H7") (pin "4") (pinfunction "4_4") (pintype "unspecified"))
      (node (ref "J1") (pin "35") (pinfunction "35_35") (pintype "unspecified"))
      (node (ref "J2") (pin "35") (pinfunction "35_35") (pintype "unspecified"))
      (node (ref "R18") (pin "2") (pinfunction "2_2") (pintype "unspecified"))
    )
    (net (code "157") (name "TX-B") (class "Default")
      (node (ref "H8") (pin "4") (pinfunction "4_4") (pintype "unspecified"))
      (node (ref "R23") (pin "2") (pinfunction "2_2") (pintype "unspecified"))
    )
    (net (code "158") (name "WAIT") (class "Default")
      (node (ref "J6") (pin "31") (pinfunction "31_31") (pintype "unspecified"))
      (node (ref "RN1") (pin "7") (pinfunction "7_7") (pintype "input"))
      (node (ref "U1") (pin "24") (pinfunction "WAIT#_24") (pintype "unspecified"))
    )
    (net (code "159") (name "WR") (class "Default")
      (node (ref "H2") (pin "32") (pinfunction "32_32") (pintype "unspecified"))
      (node (ref "J1") (pin "24") (pinfunction "24_24") (pintype "unspecified"))
      (node (ref "J2") (pin "24") (pinfunction "24_24") (pintype "unspecified"))
      (node (ref "J6") (pin "21") (pinfunction "21_21") (pintype "unspecified"))
      (node (ref "RN1") (pin "8") (pinfunction "8_8") (pintype "input"))
      (node (ref "U1") (pin "22") (pinfunction "WR#_22") (pintype "unspecified"))
      (node (ref "U14") (pin "3") (pinfunction "1B_3") (pintype "unspecified"))
      (node (ref "U14") (pin "6") (pinfunction "2B_6") (pintype "unspecified"))
      (node (ref "U3") (pin "27") (pinfunction "WE#_27") (pintype "unspecified"))
      (node (ref "U5") (pin "6") (pinfunction "WR#_6") (pintype "unspecified"))
    )
    (net (code "160") (name "unconnected-(LCD1-DB0-Pad7)") (class "Default")
      (node (ref "LCD1") (pin "7") (pinfunction "DB0_7") (pintype "unspecified"))
    )
    (net (code "161") (name "unconnected-(LCD1-DB1-Pad8)") (class "Default")
      (node (ref "LCD1") (pin "8") (pinfunction "DB1_8") (pintype "unspecified"))
    )
    (net (code "162") (name "unconnected-(LCD1-DB2-Pad9)") (class "Default")
      (node (ref "LCD1") (pin "9") (pinfunction "DB2_9") (pintype "unspecified"))
    )
    (net (code "163") (name "unconnected-(LCD1-DB3-Pad10)") (class "Default")
      (node (ref "LCD1") (pin "10") (pinfunction "DB3_10") (pintype "unspecified"))
    )
    (net (code "164") (name "unconnected-(SW1-B-Pad2)") (class "Default")
      (node (ref "SW1") (pin "2") (pinfunction "B_2") (pintype "unspecified"))
    )
    (net (code "165") (name "unconnected-(SW1-C-Pad3)") (class "Default")
      (node (ref "SW1") (pin "3") (pinfunction "C_3") (pintype "unspecified"))
    )
    (net (code "166") (name "unconnected-(SW4-B-Pad2)") (class "Default")
      (node (ref "SW4") (pin "2") (pinfunction "B_2") (pintype "unspecified"))
    )
    (net (code "167") (name "unconnected-(SW4-C-Pad3)") (class "Default")
      (node (ref "SW4") (pin "3") (pinfunction "C_3") (pintype "unspecified"))
    )
    (net (code "168") (name "unconnected-(U9-3Y-Pad6)") (class "Default")
      (node (ref "U9") (pin "6") (pinfunction "3Y_6") (pintype "unspecified"))
    )
    (net (code "169") (name "unconnected-(U9-4Y-Pad8)") (class "Default")
      (node (ref "U9") (pin "8") (pinfunction "4Y_8") (pintype "unspecified"))
    )
    (net (code "170") (name "unconnected-(U9-5Y-Pad10)") (class "Default")
      (node (ref "U9") (pin "10") (pinfunction "5Y_10") (pintype "unspecified"))
    )
    (net (code "171") (name "unconnected-(U10-3Y-Pad8)") (class "Default")
      (node (ref "U10") (pin "8") (pinfunction "3Y_8") (pintype "unspecified"))
    )
    (net (code "172") (name "unconnected-(U11-2Q#-Pad8)") (class "Default")
      (node (ref "U11") (pin "8") (pinfunction "2Q#_8") (pintype "unspecified"))
    )
    (net (code "173") (name "unconnected-(U11-2Q-Pad9)") (class "Default")
      (node (ref "U11") (pin "9") (pinfunction "2Q_9") (pintype "unspecified"))
    )
    (net (code "174") (name "unconnected-(X6-Pad2)") (class "Default")
      (node (ref "X6") (pin "2") (pinfunction "2_2") (pintype "unspecified"))
    )
  )
)
